# dw08a4lyr.net
KiCad netlist of a schematic drawn in EAGLE
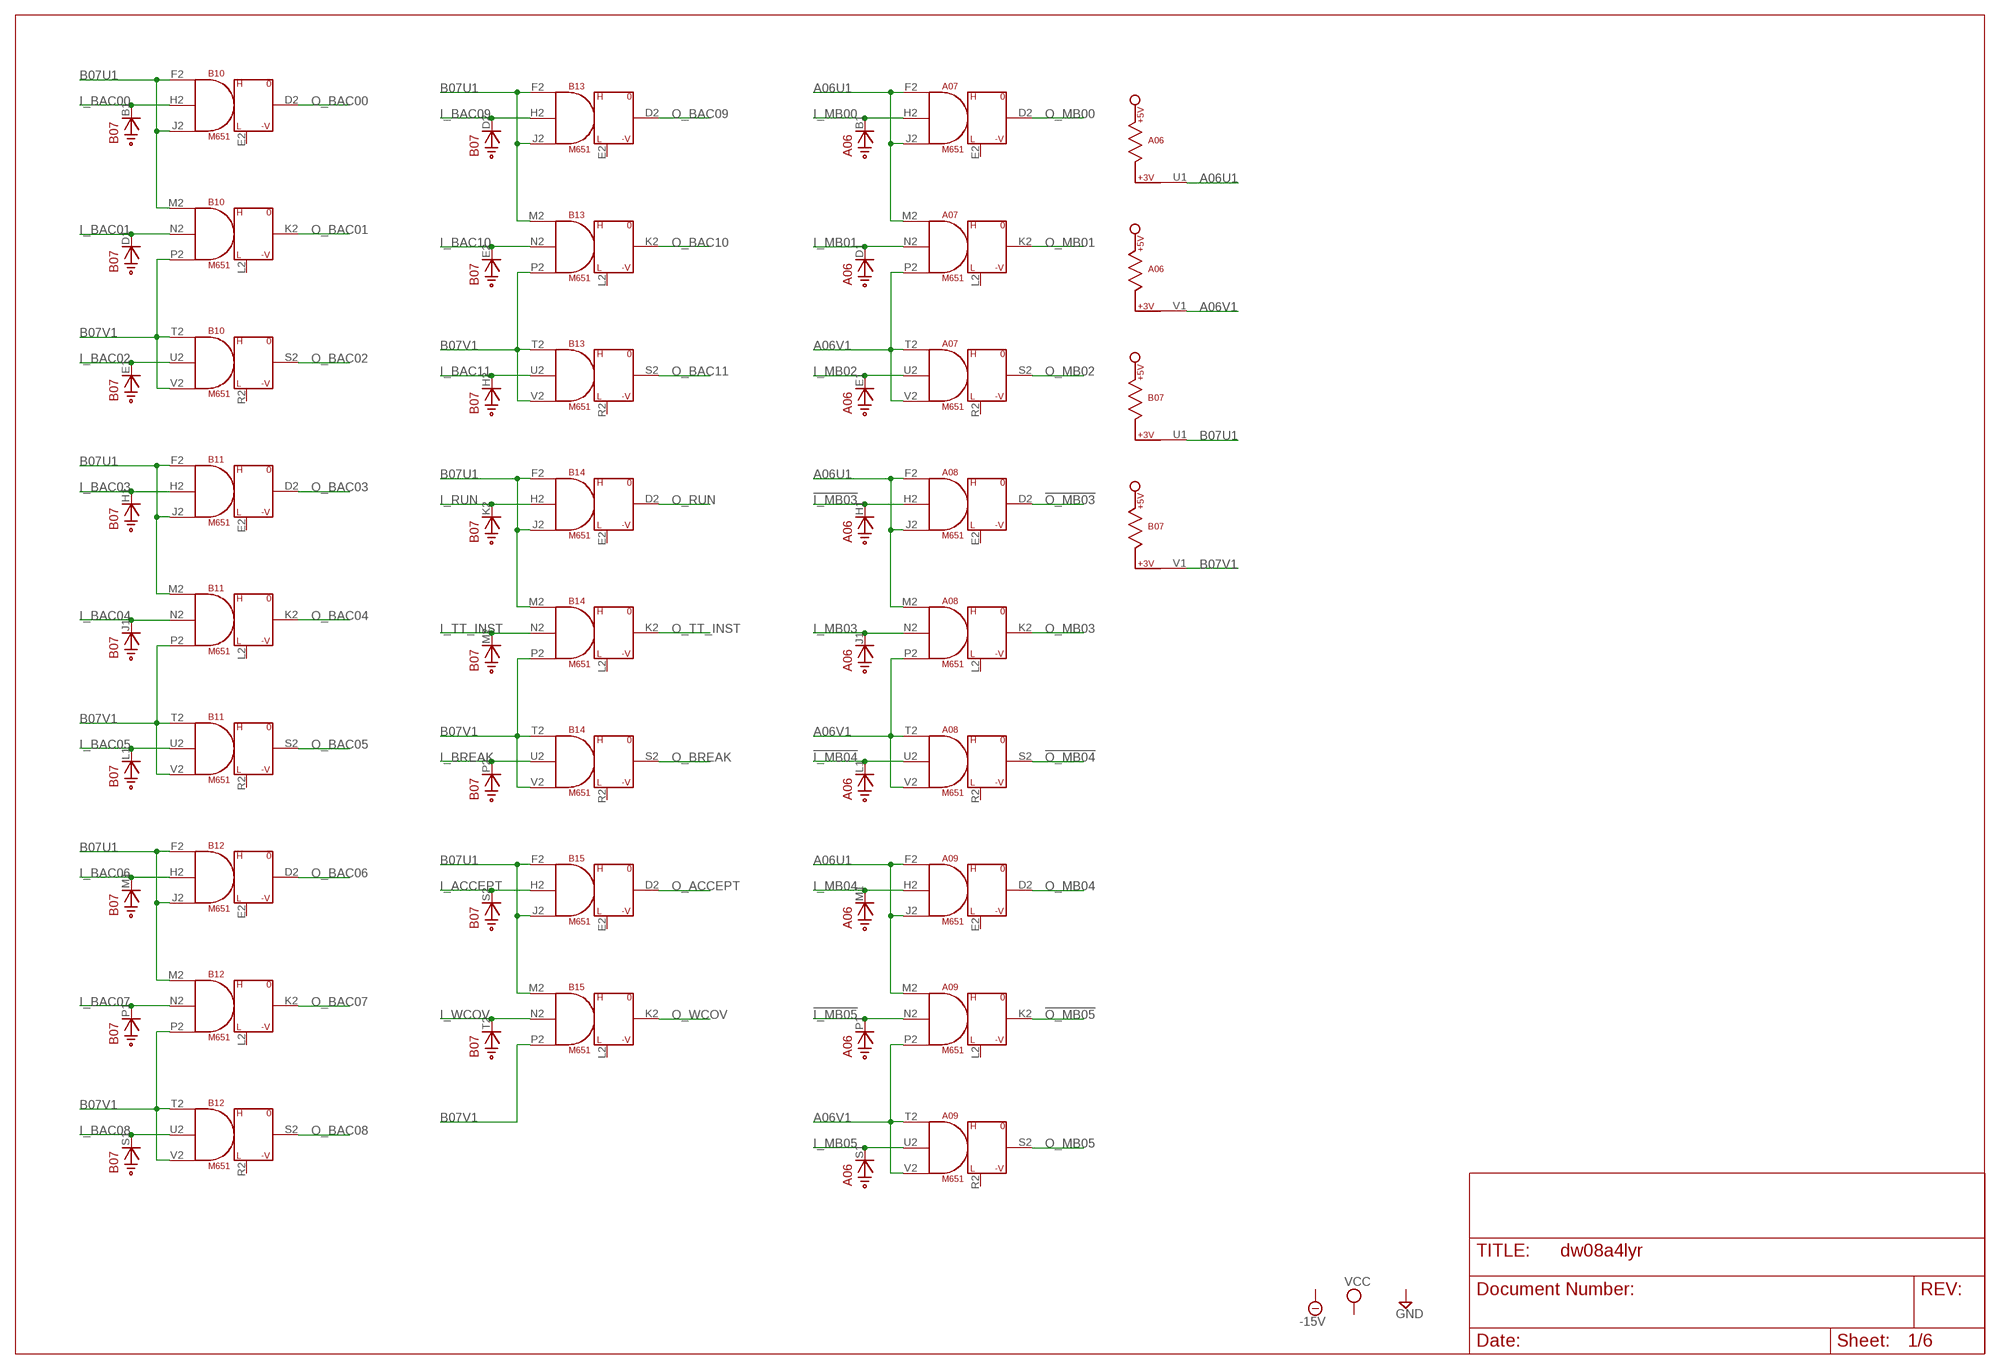
[diagram p0: schematic, sheet 1]
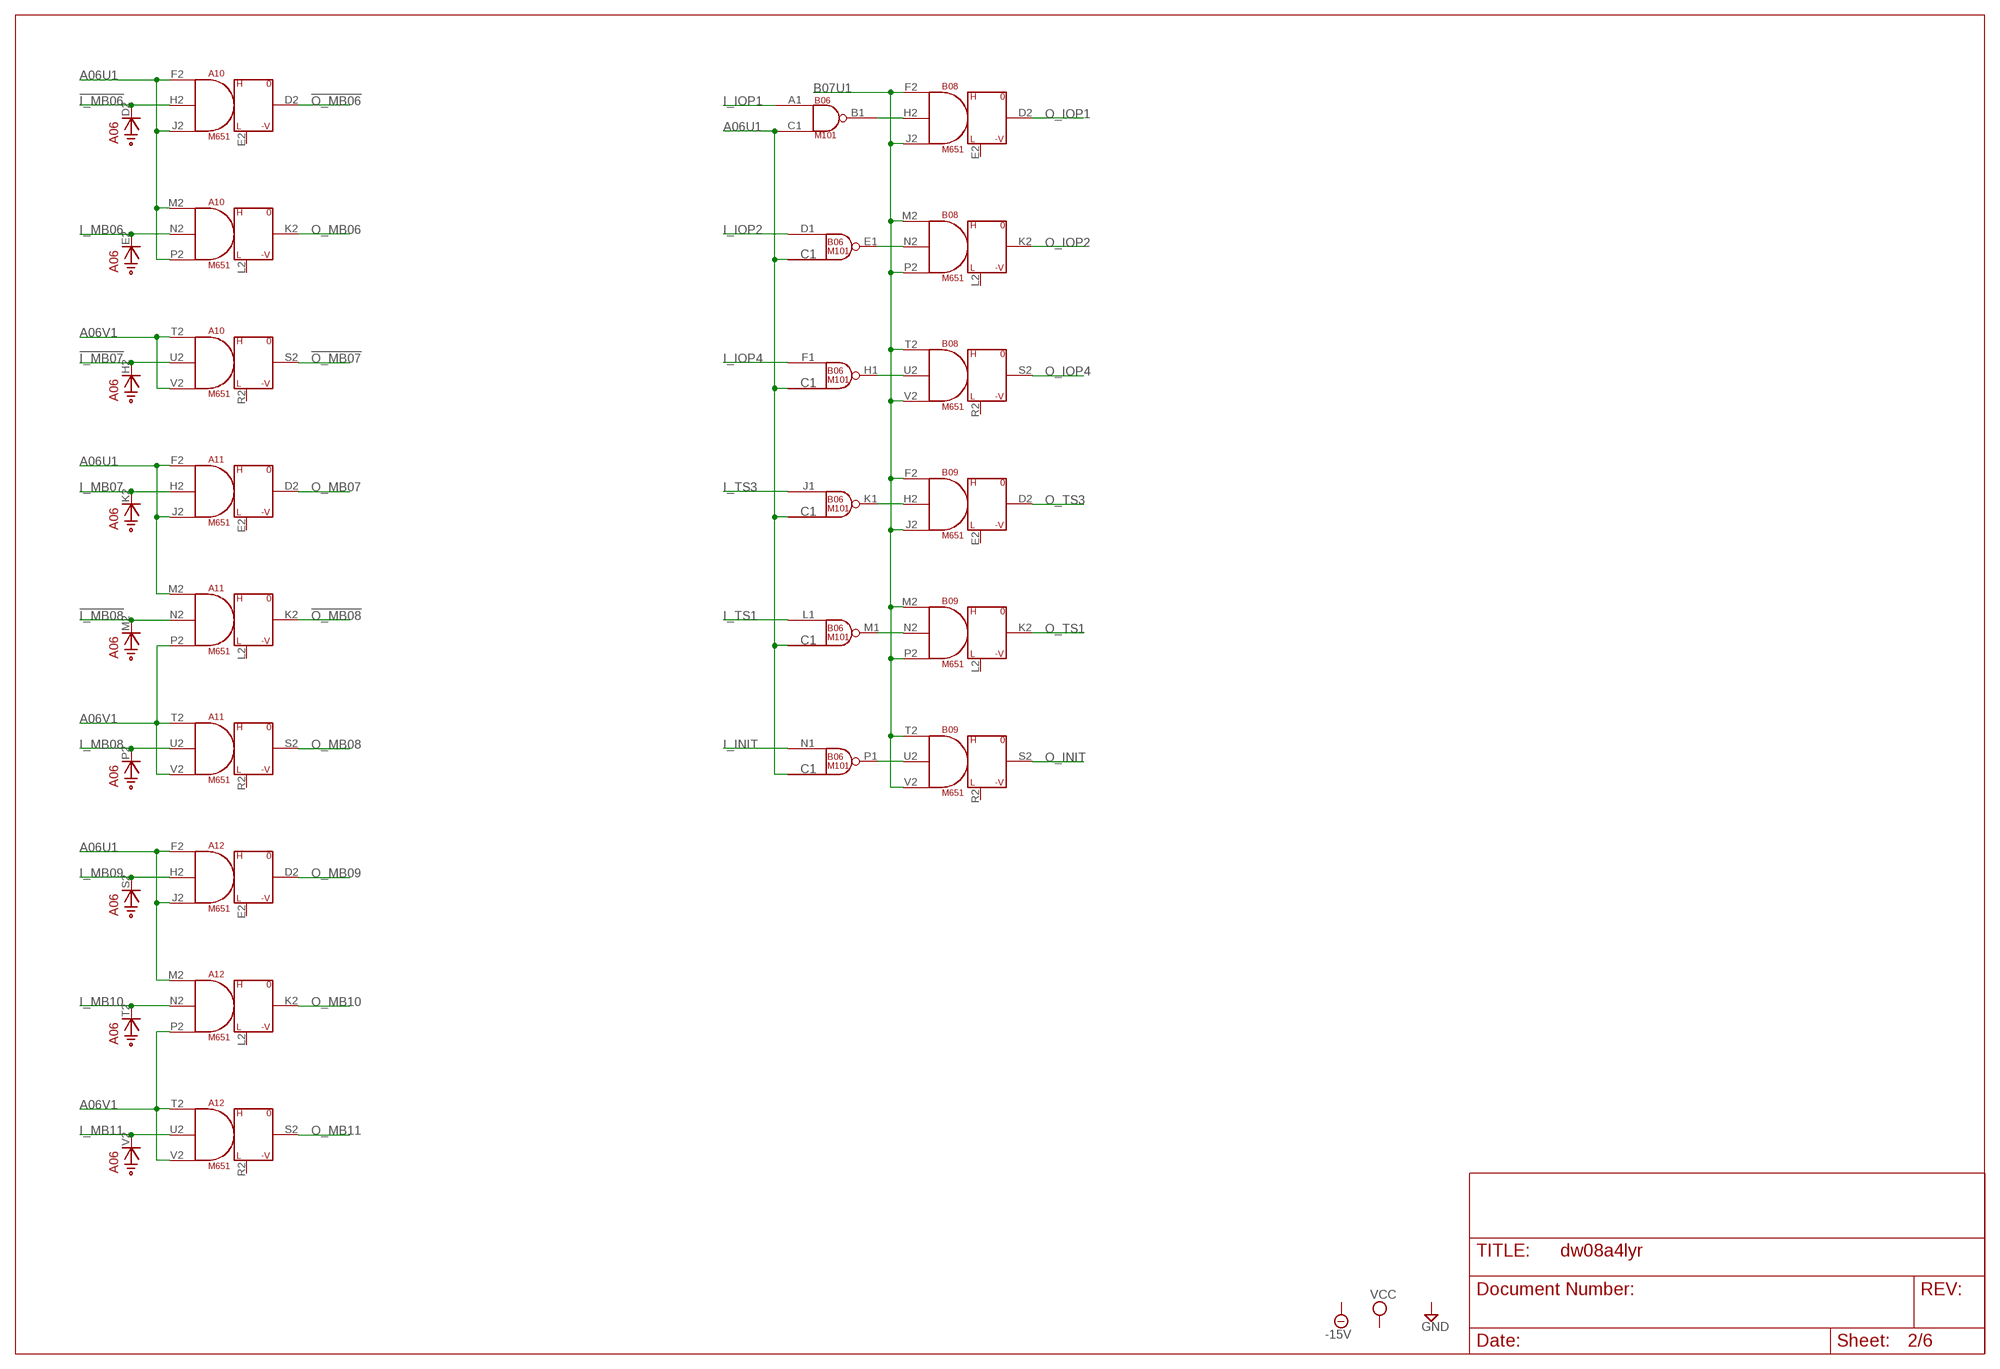
[diagram p1: schematic, sheet 2]
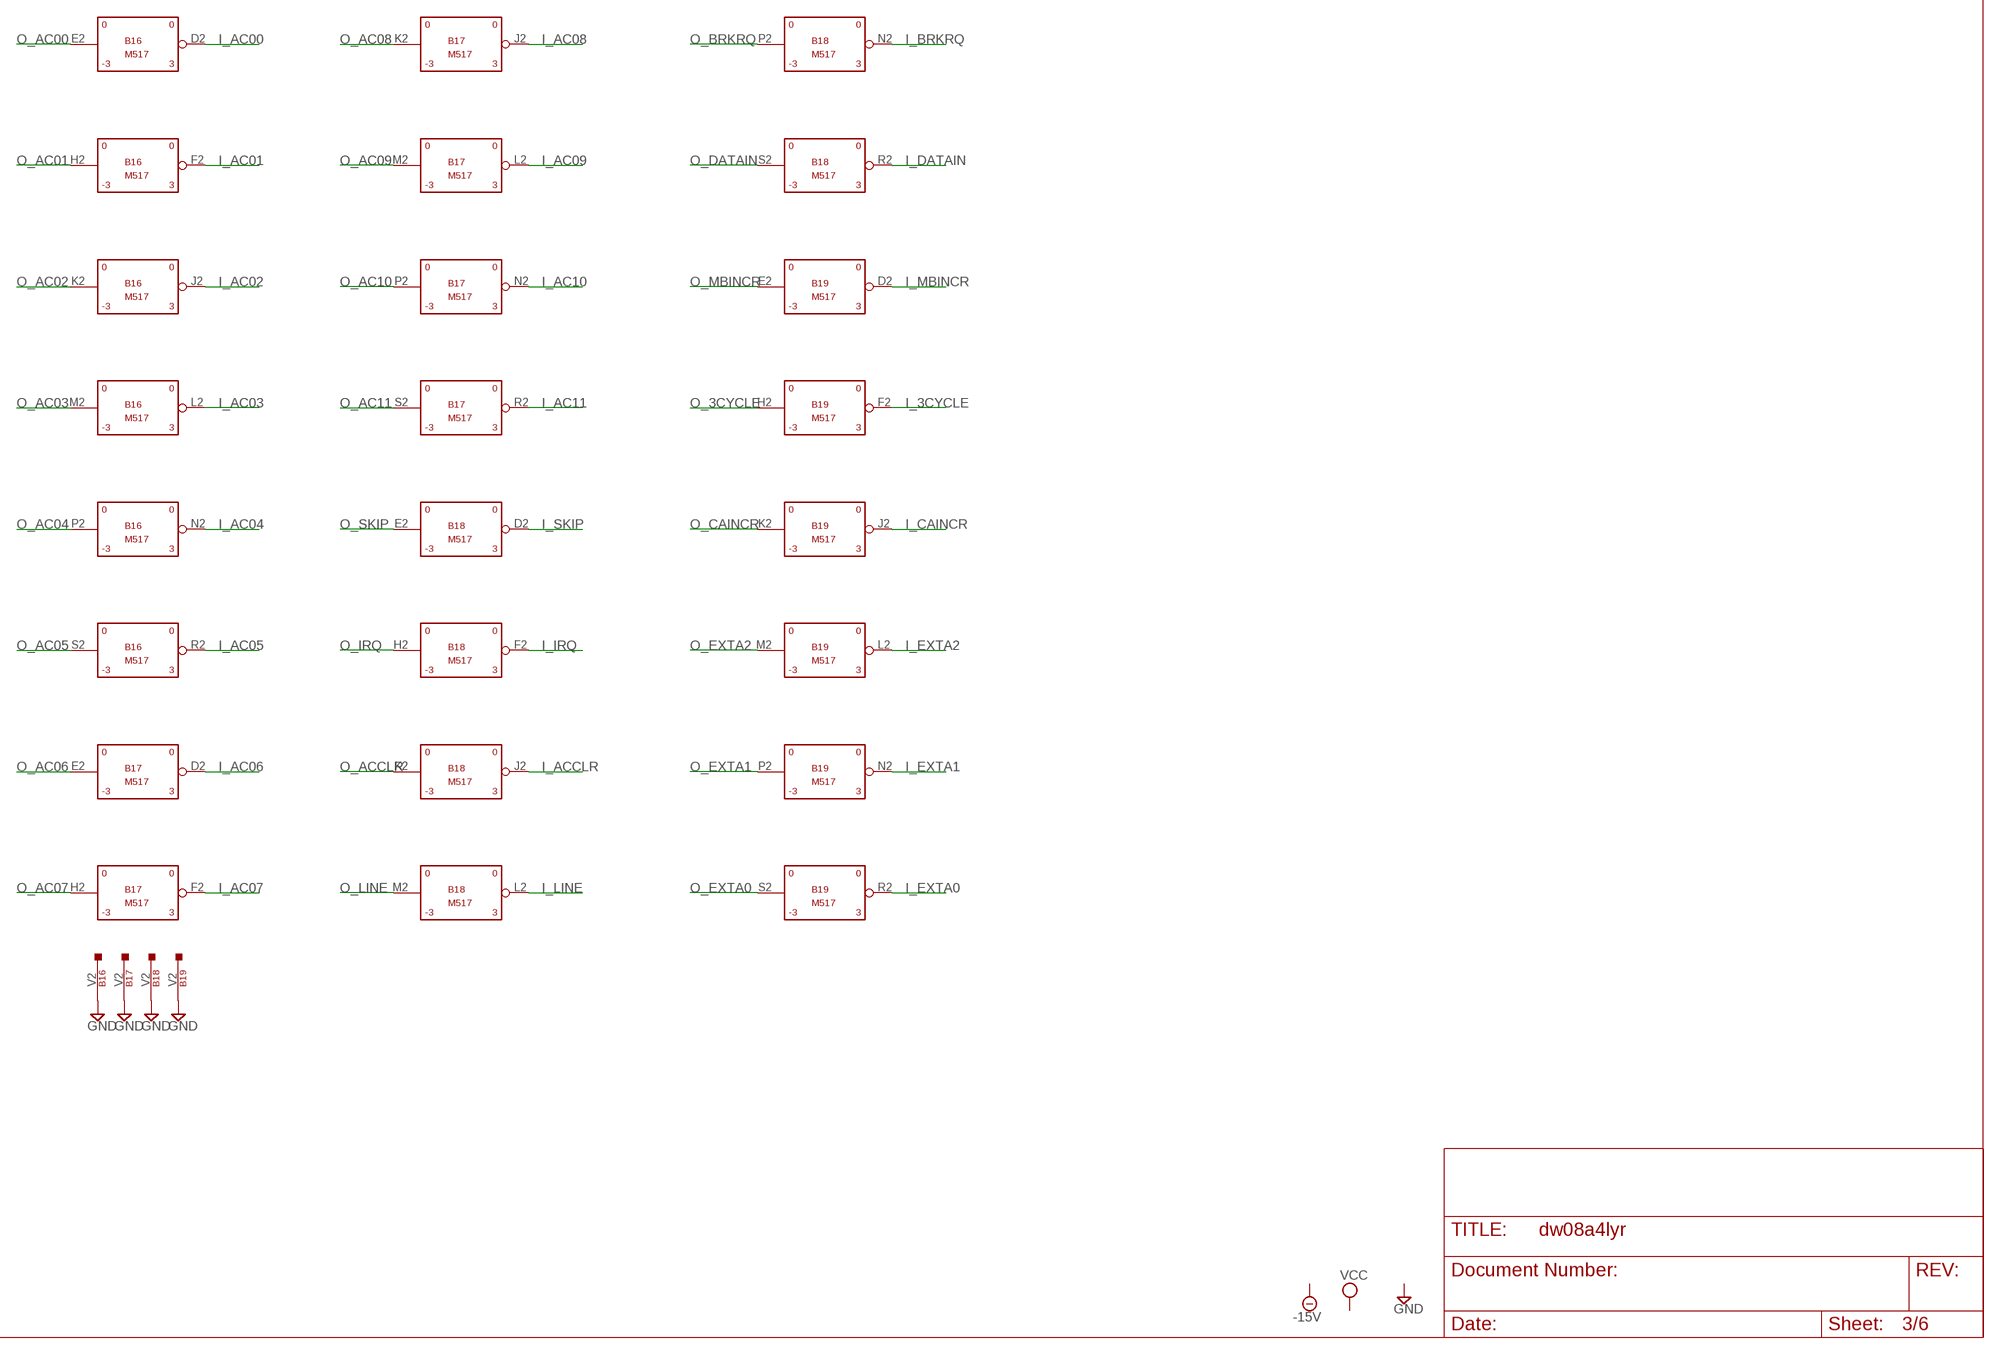
[diagram p2: schematic, sheet 3]
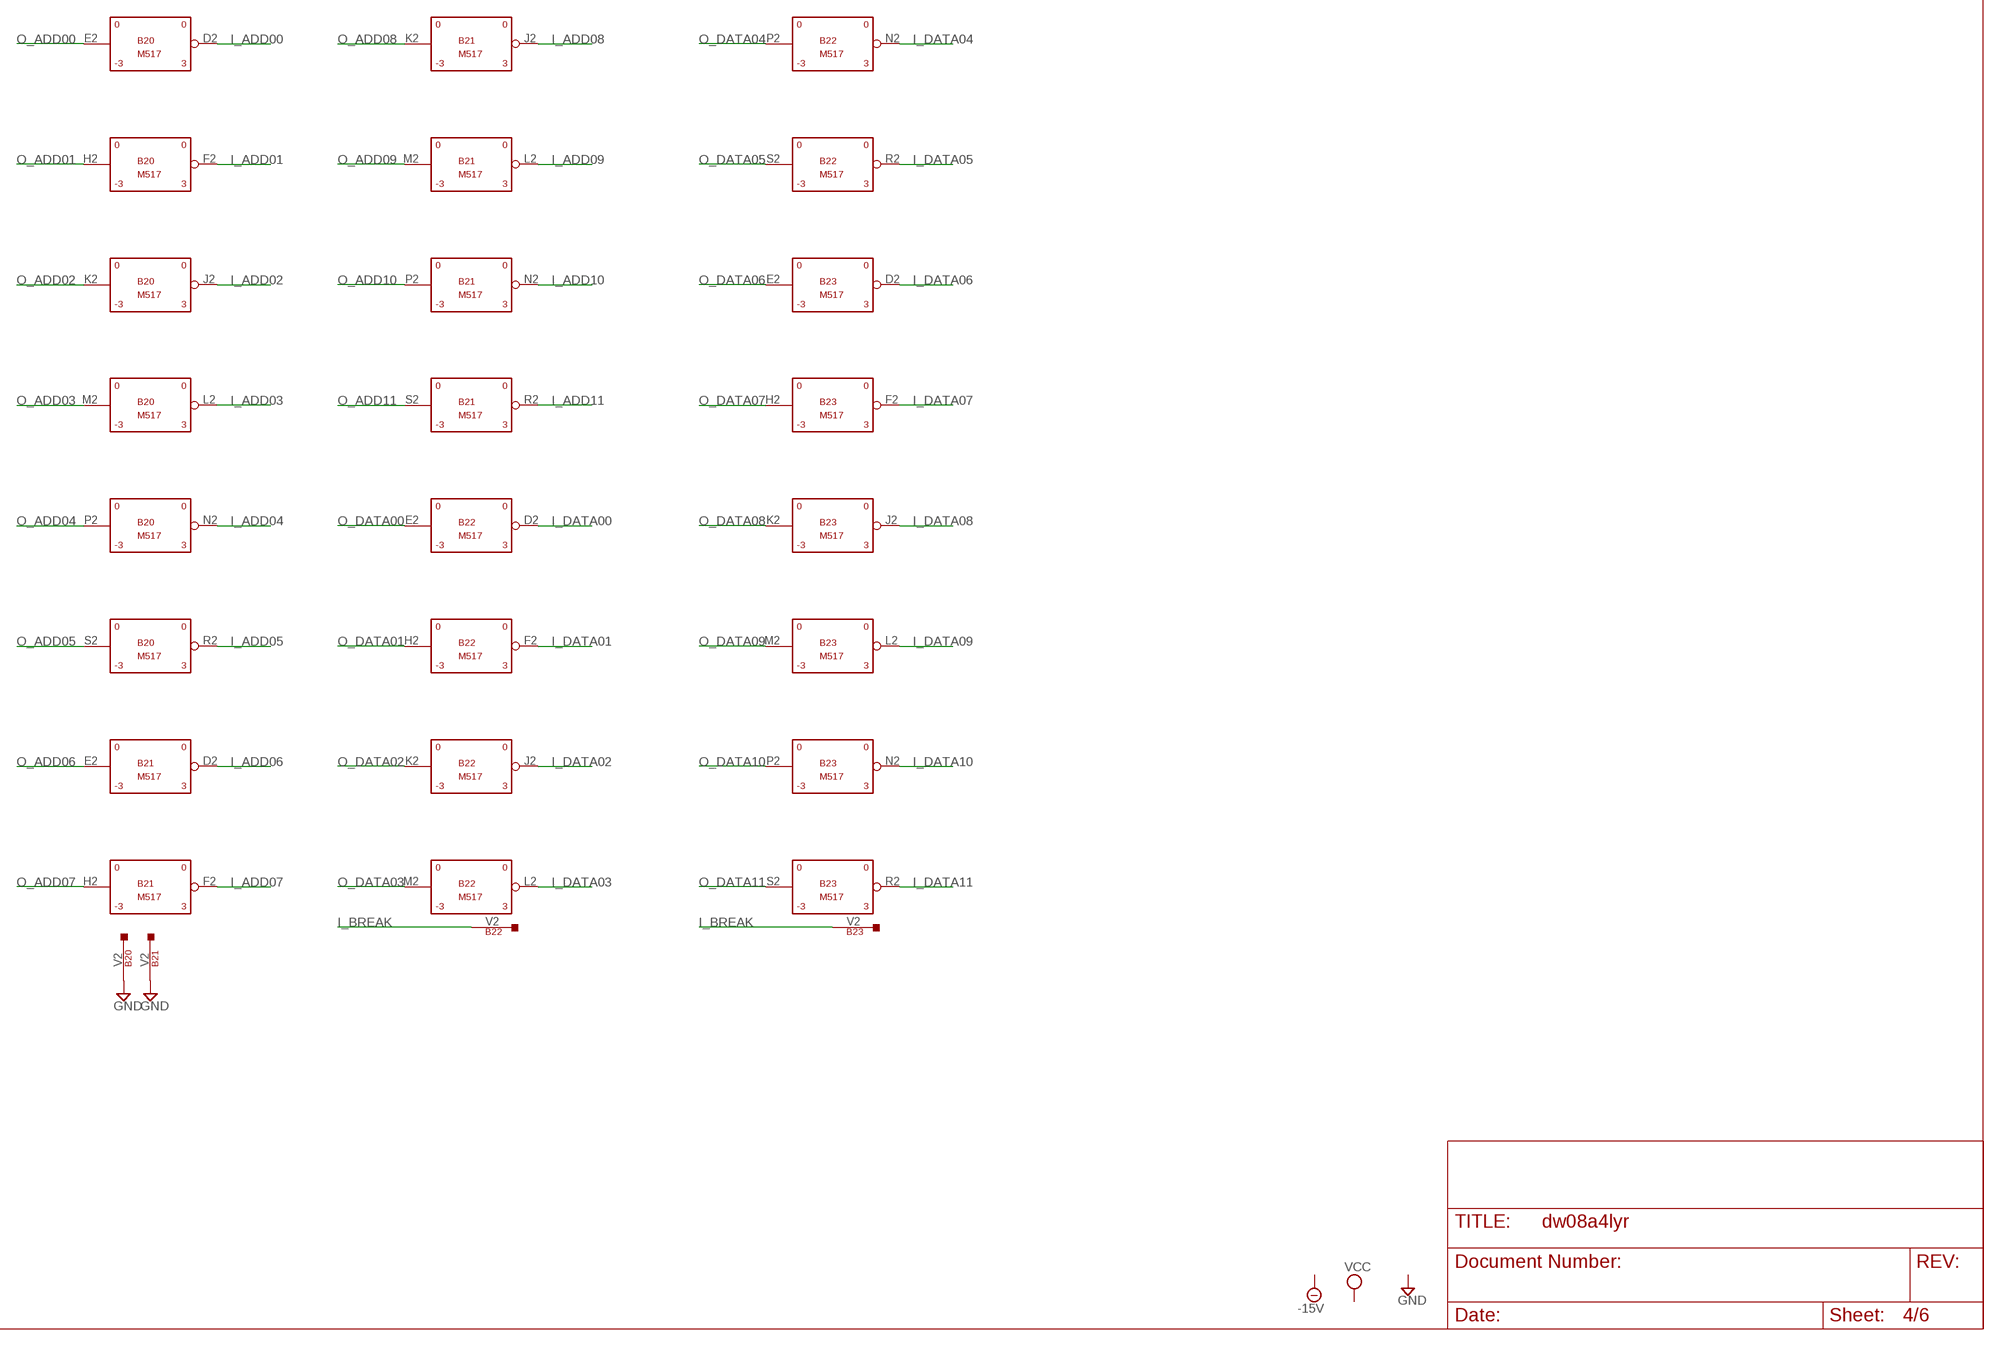
[diagram p3: schematic, sheet 4]
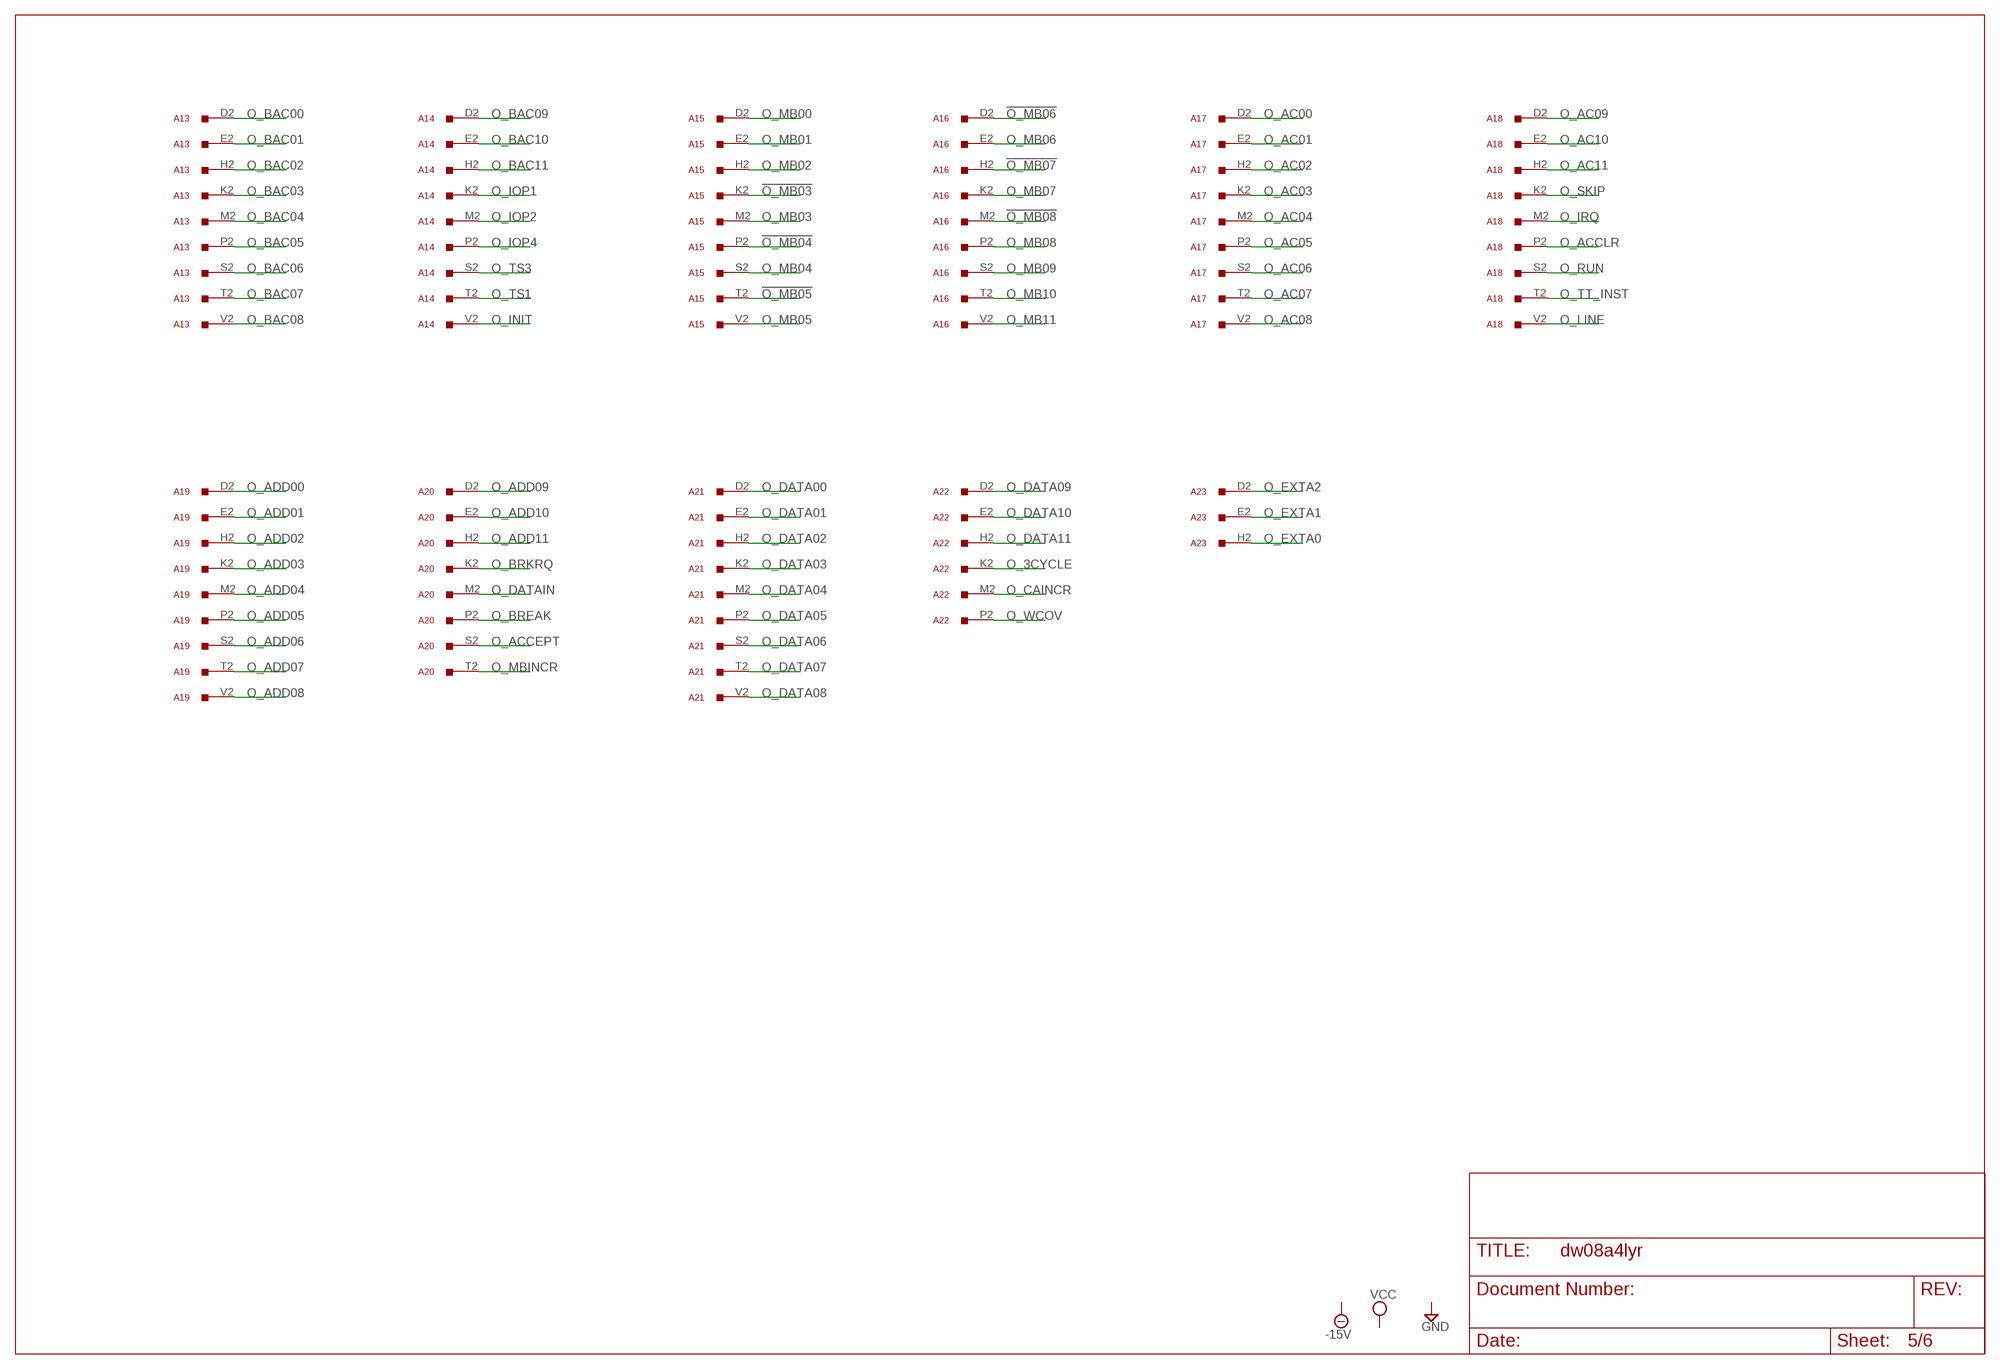
[diagram p4: schematic, sheet 5]
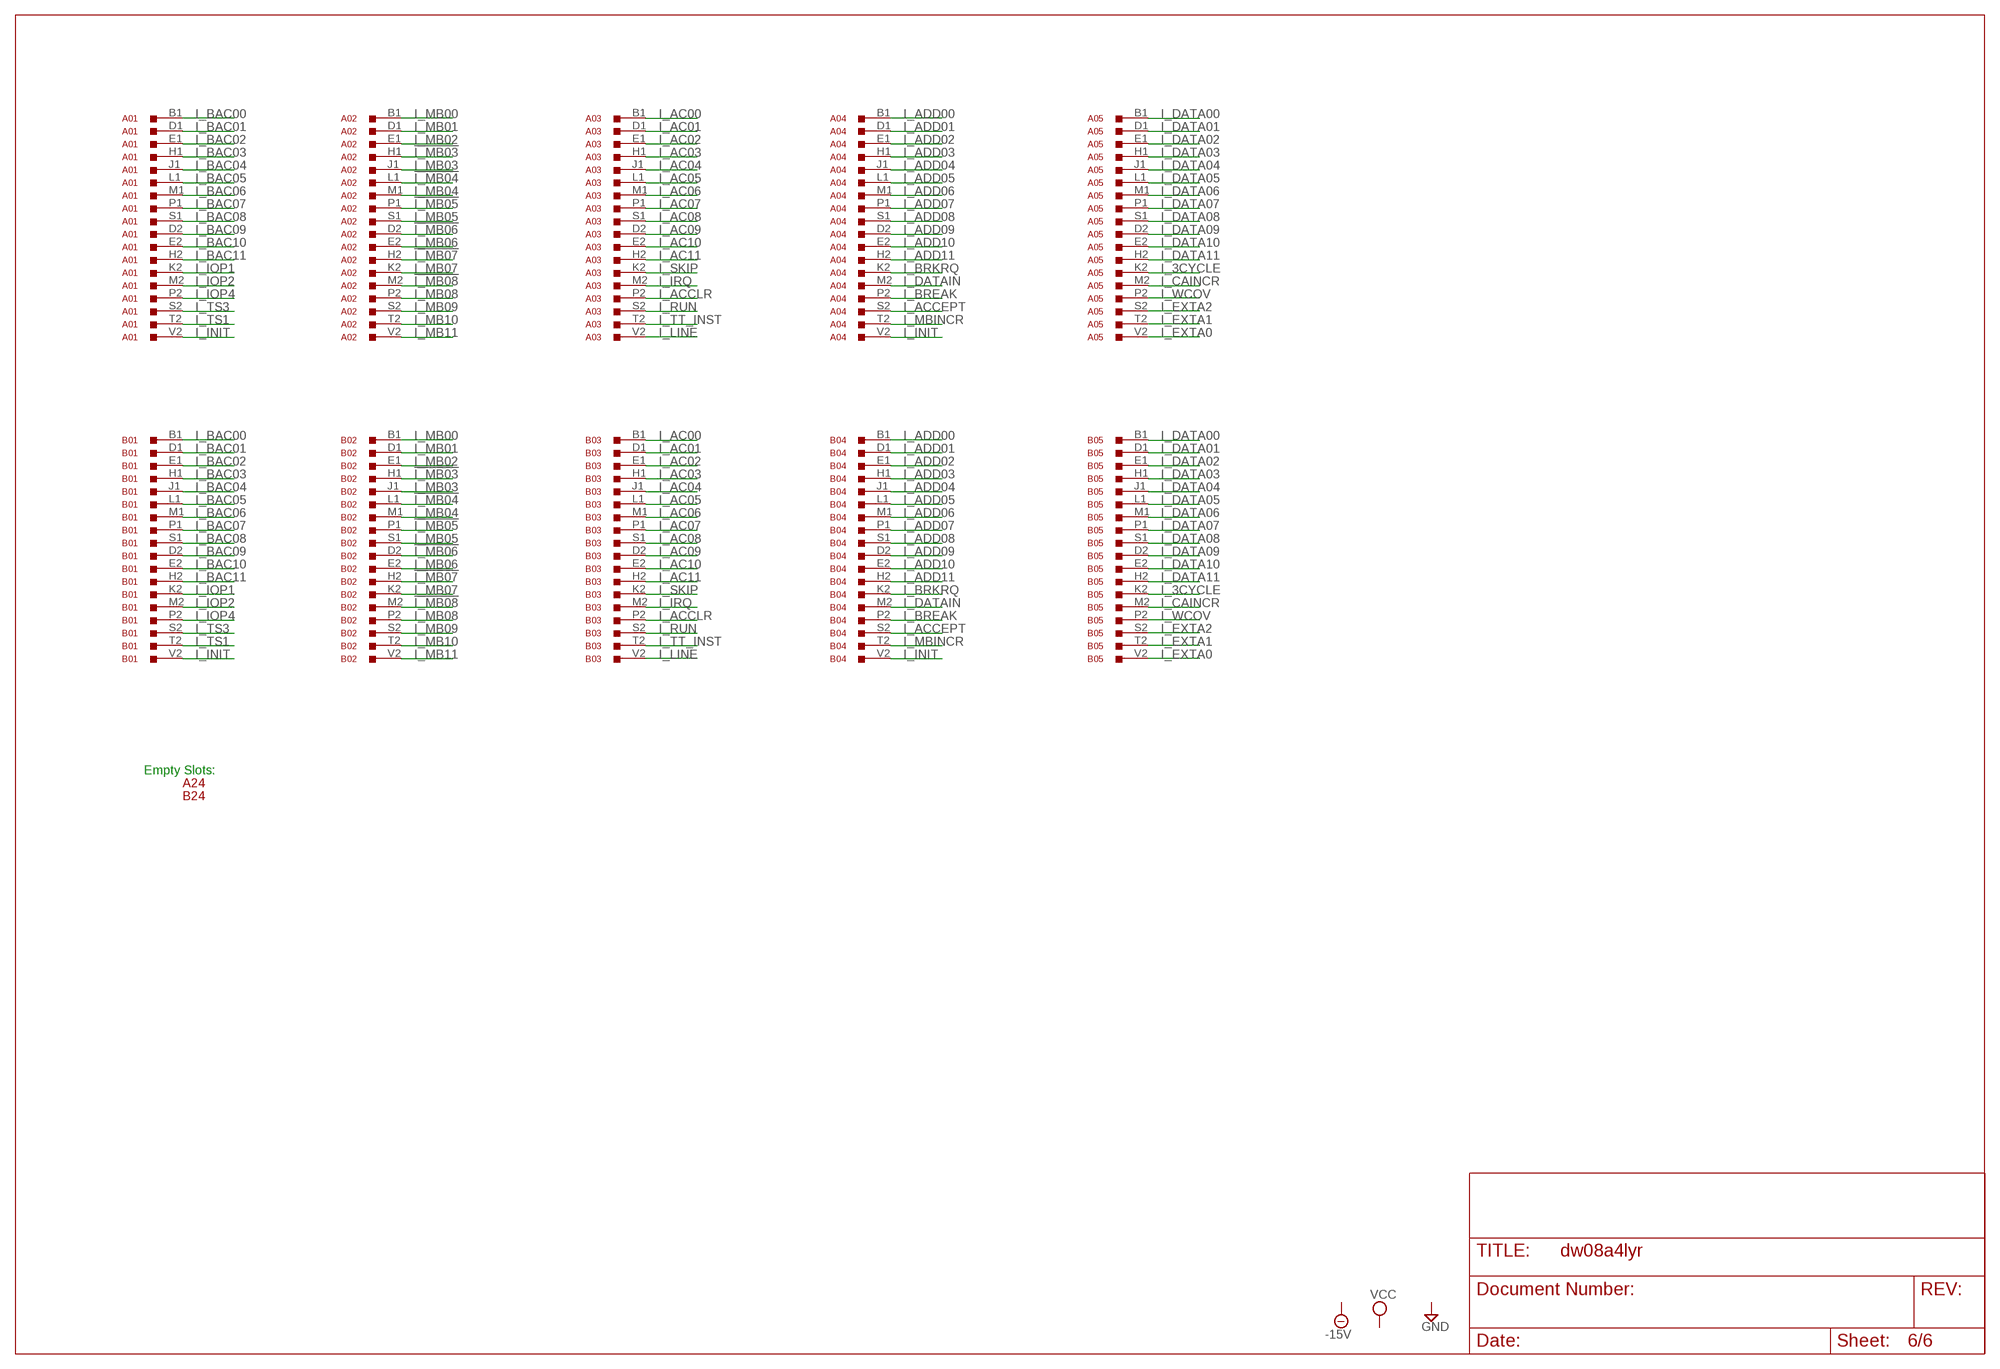
[diagram p5: schematic, sheet 6]

(export (version "E")
  (design (tool "Eeschema 10.0.6"))
  (components
    (comp (ref "A06")
      (value "M907")
      (footprint "eagle-import:H807")
      (libsource (lib "eagle-import") (part "M907"))
    )
    (comp (ref "A10")
      (value "M651")
      (footprint "eagle-import:H807")
      (libsource (lib "eagle-import") (part "M651"))
    )
    (comp (ref "A11")
      (value "M651")
      (footprint "eagle-import:H807")
      (libsource (lib "eagle-import") (part "M651"))
    )
    (comp (ref "A12")
      (value "M651")
      (footprint "eagle-import:H807")
      (libsource (lib "eagle-import") (part "M651"))
    )
    (comp (ref "B06")
      (value "M101")
      (footprint "eagle-import:H807")
      (libsource (lib "eagle-import") (part "M101"))
    )
    (comp (ref "B08")
      (value "M651")
      (footprint "eagle-import:H807")
      (libsource (lib "eagle-import") (part "M651"))
    )
    (comp (ref "B09")
      (value "M651")
      (footprint "eagle-import:H807")
      (libsource (lib "eagle-import") (part "M651"))
    )
    (comp (ref "A01")
      (value "M903")
      (footprint "eagle-import:H807")
      (libsource (lib "eagle-import") (part "M903"))
    )
    (comp (ref "A02")
      (value "M903")
      (footprint "eagle-import:H807")
      (libsource (lib "eagle-import") (part "M903"))
    )
    (comp (ref "A03")
      (value "M903")
      (footprint "eagle-import:H807")
      (libsource (lib "eagle-import") (part "M903"))
    )
    (comp (ref "A04")
      (value "M903")
      (footprint "eagle-import:H807")
      (libsource (lib "eagle-import") (part "M903"))
    )
    (comp (ref "A05")
      (value "M903")
      (footprint "eagle-import:H807")
      (libsource (lib "eagle-import") (part "M903"))
    )
    (comp (ref "A24")
      (value "H807")
      (footprint "eagle-import:H807")
      (libsource (lib "eagle-import") (part "H807"))
    )
    (comp (ref "B01")
      (value "M903")
      (footprint "eagle-import:H807")
      (libsource (lib "eagle-import") (part "M903"))
    )
    (comp (ref "B02")
      (value "M903")
      (footprint "eagle-import:H807")
      (libsource (lib "eagle-import") (part "M903"))
    )
    (comp (ref "B03")
      (value "M903")
      (footprint "eagle-import:H807")
      (libsource (lib "eagle-import") (part "M903"))
    )
    (comp (ref "B04")
      (value "M903")
      (footprint "eagle-import:H807")
      (libsource (lib "eagle-import") (part "M903"))
    )
    (comp (ref "B05")
      (value "M903")
      (footprint "eagle-import:H807")
      (libsource (lib "eagle-import") (part "M903"))
    )
    (comp (ref "B24")
      (value "H807")
      (footprint "eagle-import:H807")
      (libsource (lib "eagle-import") (part "H807"))
    )
    (comp (ref "A07")
      (value "M651")
      (footprint "eagle-import:H807")
      (libsource (lib "eagle-import") (part "M651"))
    )
    (comp (ref "A08")
      (value "M651")
      (footprint "eagle-import:H807")
      (libsource (lib "eagle-import") (part "M651"))
    )
    (comp (ref "A09")
      (value "M651")
      (footprint "eagle-import:H807")
      (libsource (lib "eagle-import") (part "M651"))
    )
    (comp (ref "B07")
      (value "M907")
      (footprint "eagle-import:H807")
      (libsource (lib "eagle-import") (part "M907"))
    )
    (comp (ref "B10")
      (value "M651")
      (footprint "eagle-import:H807")
      (libsource (lib "eagle-import") (part "M651"))
    )
    (comp (ref "B11")
      (value "M651")
      (footprint "eagle-import:H807")
      (libsource (lib "eagle-import") (part "M651"))
    )
    (comp (ref "B12")
      (value "M651")
      (footprint "eagle-import:H807")
      (libsource (lib "eagle-import") (part "M651"))
    )
    (comp (ref "B13")
      (value "M651")
      (footprint "eagle-import:H807")
      (libsource (lib "eagle-import") (part "M651"))
    )
    (comp (ref "B14")
      (value "M651")
      (footprint "eagle-import:H807")
      (libsource (lib "eagle-import") (part "M651"))
    )
    (comp (ref "B15")
      (value "M651")
      (footprint "eagle-import:H807")
      (libsource (lib "eagle-import") (part "M651"))
    )
    (comp (ref "B20")
      (value "M517")
      (footprint "eagle-import:H807")
      (libsource (lib "eagle-import") (part "M517"))
    )
    (comp (ref "B21")
      (value "M517")
      (footprint "eagle-import:H807")
      (libsource (lib "eagle-import") (part "M517"))
    )
    (comp (ref "B22")
      (value "M517")
      (footprint "eagle-import:H807")
      (libsource (lib "eagle-import") (part "M517"))
    )
    (comp (ref "B23")
      (value "M517")
      (footprint "eagle-import:H807")
      (libsource (lib "eagle-import") (part "M517"))
    )
    (comp (ref "A13")
      (value "W011")
      (footprint "eagle-import:H807")
      (libsource (lib "eagle-import") (part "W011"))
    )
    (comp (ref "A14")
      (value "W011")
      (footprint "eagle-import:H807")
      (libsource (lib "eagle-import") (part "W011"))
    )
    (comp (ref "A15")
      (value "W011")
      (footprint "eagle-import:H807")
      (libsource (lib "eagle-import") (part "W011"))
    )
    (comp (ref "A16")
      (value "W011")
      (footprint "eagle-import:H807")
      (libsource (lib "eagle-import") (part "W011"))
    )
    (comp (ref "A17")
      (value "W011")
      (footprint "eagle-import:H807")
      (libsource (lib "eagle-import") (part "W011"))
    )
    (comp (ref "A18")
      (value "W011")
      (footprint "eagle-import:H807")
      (libsource (lib "eagle-import") (part "W011"))
    )
    (comp (ref "A19")
      (value "W011")
      (footprint "eagle-import:H807")
      (libsource (lib "eagle-import") (part "W011"))
    )
    (comp (ref "A20")
      (value "W011")
      (footprint "eagle-import:H807")
      (libsource (lib "eagle-import") (part "W011"))
    )
    (comp (ref "A21")
      (value "W011")
      (footprint "eagle-import:H807")
      (libsource (lib "eagle-import") (part "W011"))
    )
    (comp (ref "A22")
      (value "W011")
      (footprint "eagle-import:H807")
      (libsource (lib "eagle-import") (part "W011"))
    )
    (comp (ref "A23")
      (value "W011")
      (footprint "eagle-import:H807")
      (libsource (lib "eagle-import") (part "W011"))
    )
    (comp (ref "B16")
      (value "M517")
      (footprint "eagle-import:H807")
      (libsource (lib "eagle-import") (part "M517"))
    )
    (comp (ref "B17")
      (value "M517")
      (footprint "eagle-import:H807")
      (libsource (lib "eagle-import") (part "M517"))
    )
    (comp (ref "B18")
      (value "M517")
      (footprint "eagle-import:H807")
      (libsource (lib "eagle-import") (part "M517"))
    )
    (comp (ref "B19")
      (value "M517")
      (footprint "eagle-import:H807")
      (libsource (lib "eagle-import") (part "M517"))
    )
  )
  (nets
    (net (code "2") (name "A06U1") (class "Default")
      (node (ref "A06") (pin "U1") (pinfunction "P$1_U1") (pintype "passive"))
      (node (ref "A07") (pin "F2") (pinfunction "IN1_F2") (pintype "input"))
      (node (ref "A07") (pin "J2") (pinfunction "IN3_J2") (pintype "input"))
      (node (ref "A07") (pin "M2") (pinfunction "IN1_M2") (pintype "input"))
      (node (ref "A08") (pin "F2") (pinfunction "IN1_F2") (pintype "input"))
      (node (ref "A08") (pin "J2") (pinfunction "IN3_J2") (pintype "input"))
      (node (ref "A08") (pin "M2") (pinfunction "IN1_M2") (pintype "input"))
      (node (ref "A09") (pin "F2") (pinfunction "IN1_F2") (pintype "input"))
      (node (ref "A09") (pin "J2") (pinfunction "IN3_J2") (pintype "input"))
      (node (ref "A09") (pin "M2") (pinfunction "IN1_M2") (pintype "input"))
      (node (ref "A10") (pin "F2") (pinfunction "IN1_F2") (pintype "input"))
      (node (ref "A10") (pin "J2") (pinfunction "IN3_J2") (pintype "input"))
      (node (ref "A10") (pin "M2") (pinfunction "IN1_M2") (pintype "input"))
      (node (ref "A10") (pin "P2") (pinfunction "IN3_P2") (pintype "input"))
      (node (ref "A11") (pin "F2") (pinfunction "IN1_F2") (pintype "input"))
      (node (ref "A11") (pin "J2") (pinfunction "IN3_J2") (pintype "input"))
      (node (ref "A11") (pin "M2") (pinfunction "IN1_M2") (pintype "input"))
      (node (ref "A12") (pin "F2") (pinfunction "IN1_F2") (pintype "input"))
      (node (ref "A12") (pin "J2") (pinfunction "IN3_J2") (pintype "input"))
      (node (ref "A12") (pin "M2") (pinfunction "IN1_M2") (pintype "input"))
      (node (ref "B06") (pin "C1") (pinfunction "IN2_C1") (pintype "input"))
    )
    (net (code "3") (name "A06V1") (class "Default")
      (node (ref "A06") (pin "V1") (pinfunction "P$1_V1") (pintype "passive"))
      (node (ref "A07") (pin "P2") (pinfunction "IN3_P2") (pintype "input"))
      (node (ref "A07") (pin "T2") (pinfunction "IN1_T2") (pintype "input"))
      (node (ref "A07") (pin "V2") (pinfunction "IN3_V2") (pintype "input"))
      (node (ref "A08") (pin "P2") (pinfunction "IN3_P2") (pintype "input"))
      (node (ref "A08") (pin "T2") (pinfunction "IN1_T2") (pintype "input"))
      (node (ref "A08") (pin "V2") (pinfunction "IN3_V2") (pintype "input"))
      (node (ref "A09") (pin "P2") (pinfunction "IN3_P2") (pintype "input"))
      (node (ref "A09") (pin "T2") (pinfunction "IN1_T2") (pintype "input"))
      (node (ref "A09") (pin "V2") (pinfunction "IN3_V2") (pintype "input"))
      (node (ref "A10") (pin "T2") (pinfunction "IN1_T2") (pintype "input"))
      (node (ref "A10") (pin "V2") (pinfunction "IN3_V2") (pintype "input"))
      (node (ref "A11") (pin "P2") (pinfunction "IN3_P2") (pintype "input"))
      (node (ref "A11") (pin "T2") (pinfunction "IN1_T2") (pintype "input"))
      (node (ref "A11") (pin "V2") (pinfunction "IN3_V2") (pintype "input"))
      (node (ref "A12") (pin "P2") (pinfunction "IN3_P2") (pintype "input"))
      (node (ref "A12") (pin "T2") (pinfunction "IN1_T2") (pintype "input"))
      (node (ref "A12") (pin "V2") (pinfunction "IN3_V2") (pintype "input"))
    )
    (net (code "4") (name "B07U1") (class "Default")
      (node (ref "B07") (pin "U1") (pinfunction "P$1_U1") (pintype "passive"))
      (node (ref "B08") (pin "F2") (pinfunction "IN1_F2") (pintype "input"))
      (node (ref "B08") (pin "J2") (pinfunction "IN3_J2") (pintype "input"))
      (node (ref "B08") (pin "M2") (pinfunction "IN1_M2") (pintype "input"))
      (node (ref "B08") (pin "P2") (pinfunction "IN3_P2") (pintype "input"))
      (node (ref "B08") (pin "T2") (pinfunction "IN1_T2") (pintype "input"))
      (node (ref "B08") (pin "V2") (pinfunction "IN3_V2") (pintype "input"))
      (node (ref "B09") (pin "F2") (pinfunction "IN1_F2") (pintype "input"))
      (node (ref "B09") (pin "J2") (pinfunction "IN3_J2") (pintype "input"))
      (node (ref "B09") (pin "M2") (pinfunction "IN1_M2") (pintype "input"))
      (node (ref "B09") (pin "P2") (pinfunction "IN3_P2") (pintype "input"))
      (node (ref "B09") (pin "T2") (pinfunction "IN1_T2") (pintype "input"))
      (node (ref "B09") (pin "V2") (pinfunction "IN3_V2") (pintype "input"))
      (node (ref "B10") (pin "F2") (pinfunction "IN1_F2") (pintype "input"))
      (node (ref "B10") (pin "J2") (pinfunction "IN3_J2") (pintype "input"))
      (node (ref "B10") (pin "M2") (pinfunction "IN1_M2") (pintype "input"))
      (node (ref "B11") (pin "F2") (pinfunction "IN1_F2") (pintype "input"))
      (node (ref "B11") (pin "J2") (pinfunction "IN3_J2") (pintype "input"))
      (node (ref "B11") (pin "M2") (pinfunction "IN1_M2") (pintype "input"))
      (node (ref "B12") (pin "F2") (pinfunction "IN1_F2") (pintype "input"))
      (node (ref "B12") (pin "J2") (pinfunction "IN3_J2") (pintype "input"))
      (node (ref "B12") (pin "M2") (pinfunction "IN1_M2") (pintype "input"))
      (node (ref "B13") (pin "F2") (pinfunction "IN1_F2") (pintype "input"))
      (node (ref "B13") (pin "J2") (pinfunction "IN3_J2") (pintype "input"))
      (node (ref "B13") (pin "M2") (pinfunction "IN1_M2") (pintype "input"))
      (node (ref "B14") (pin "F2") (pinfunction "IN1_F2") (pintype "input"))
      (node (ref "B14") (pin "J2") (pinfunction "IN3_J2") (pintype "input"))
      (node (ref "B14") (pin "M2") (pinfunction "IN1_M2") (pintype "input"))
      (node (ref "B15") (pin "F2") (pinfunction "IN1_F2") (pintype "input"))
      (node (ref "B15") (pin "J2") (pinfunction "IN3_J2") (pintype "input"))
      (node (ref "B15") (pin "M2") (pinfunction "IN1_M2") (pintype "input"))
    )
    (net (code "5") (name "B07V1") (class "Default")
      (node (ref "B07") (pin "V1") (pinfunction "P$1_V1") (pintype "passive"))
      (node (ref "B10") (pin "P2") (pinfunction "IN3_P2") (pintype "input"))
      (node (ref "B10") (pin "T2") (pinfunction "IN1_T2") (pintype "input"))
      (node (ref "B10") (pin "V2") (pinfunction "IN3_V2") (pintype "input"))
      (node (ref "B11") (pin "P2") (pinfunction "IN3_P2") (pintype "input"))
      (node (ref "B11") (pin "T2") (pinfunction "IN1_T2") (pintype "input"))
      (node (ref "B11") (pin "V2") (pinfunction "IN3_V2") (pintype "input"))
      (node (ref "B12") (pin "P2") (pinfunction "IN3_P2") (pintype "input"))
      (node (ref "B12") (pin "T2") (pinfunction "IN1_T2") (pintype "input"))
      (node (ref "B12") (pin "V2") (pinfunction "IN3_V2") (pintype "input"))
      (node (ref "B13") (pin "P2") (pinfunction "IN3_P2") (pintype "input"))
      (node (ref "B13") (pin "T2") (pinfunction "IN1_T2") (pintype "input"))
      (node (ref "B13") (pin "V2") (pinfunction "IN3_V2") (pintype "input"))
      (node (ref "B14") (pin "P2") (pinfunction "IN3_P2") (pintype "input"))
      (node (ref "B14") (pin "T2") (pinfunction "IN1_T2") (pintype "input"))
      (node (ref "B14") (pin "V2") (pinfunction "IN3_V2") (pintype "input"))
      (node (ref "B15") (pin "P2") (pinfunction "IN3_P2") (pintype "input"))
    )
    (net (code "6") (name "GND") (class "Default")
      (node (ref "B16") (pin "V2") (pinfunction "P$1_V2") (pintype "input"))
      (node (ref "B17") (pin "V2") (pinfunction "P$1_V2") (pintype "input"))
      (node (ref "B18") (pin "V2") (pinfunction "P$1_V2") (pintype "input"))
      (node (ref "B19") (pin "V2") (pinfunction "P$1_V2") (pintype "input"))
      (node (ref "B20") (pin "V2") (pinfunction "P$1_V2") (pintype "input"))
      (node (ref "B21") (pin "V2") (pinfunction "P$1_V2") (pintype "input"))
    )
    (net (code "7") (name "I_3CYCLE") (class "Default")
      (node (ref "A05") (pin "K2") (pinfunction "P$2_K2") (pintype "bidirectional"))
      (node (ref "B05") (pin "K2") (pinfunction "P$2_K2") (pintype "bidirectional"))
      (node (ref "B19") (pin "F2") (pinfunction "OUT_F2") (pintype "output"))
    )
    (net (code "8") (name "I_AC00") (class "Default")
      (node (ref "A03") (pin "B1") (pinfunction "P$2_B1") (pintype "bidirectional"))
      (node (ref "B03") (pin "B1") (pinfunction "P$2_B1") (pintype "bidirectional"))
      (node (ref "B16") (pin "D2") (pinfunction "OUT_D2") (pintype "output"))
    )
    (net (code "9") (name "I_AC01") (class "Default")
      (node (ref "A03") (pin "D1") (pinfunction "P$2_D1") (pintype "bidirectional"))
      (node (ref "B03") (pin "D1") (pinfunction "P$2_D1") (pintype "bidirectional"))
      (node (ref "B16") (pin "F2") (pinfunction "OUT_F2") (pintype "output"))
    )
    (net (code "10") (name "I_AC02") (class "Default")
      (node (ref "A03") (pin "E1") (pinfunction "P$2_E1") (pintype "bidirectional"))
      (node (ref "B03") (pin "E1") (pinfunction "P$2_E1") (pintype "bidirectional"))
      (node (ref "B16") (pin "J2") (pinfunction "OUT_J2") (pintype "output"))
    )
    (net (code "11") (name "I_AC03") (class "Default")
      (node (ref "A03") (pin "H1") (pinfunction "P$2_H1") (pintype "bidirectional"))
      (node (ref "B03") (pin "H1") (pinfunction "P$2_H1") (pintype "bidirectional"))
      (node (ref "B16") (pin "L2") (pinfunction "OUT_L2") (pintype "output"))
    )
    (net (code "12") (name "I_AC04") (class "Default")
      (node (ref "A03") (pin "J1") (pinfunction "P$2_J1") (pintype "bidirectional"))
      (node (ref "B03") (pin "J1") (pinfunction "P$2_J1") (pintype "bidirectional"))
      (node (ref "B16") (pin "N2") (pinfunction "OUT_N2") (pintype "output"))
    )
    (net (code "13") (name "I_AC05") (class "Default")
      (node (ref "A03") (pin "L1") (pinfunction "P$2_L1") (pintype "bidirectional"))
      (node (ref "B03") (pin "L1") (pinfunction "P$2_L1") (pintype "bidirectional"))
      (node (ref "B16") (pin "R2") (pinfunction "OUT_R2") (pintype "output"))
    )
    (net (code "14") (name "I_AC06") (class "Default")
      (node (ref "A03") (pin "M1") (pinfunction "P$2_M1") (pintype "bidirectional"))
      (node (ref "B03") (pin "M1") (pinfunction "P$2_M1") (pintype "bidirectional"))
      (node (ref "B17") (pin "D2") (pinfunction "OUT_D2") (pintype "output"))
    )
    (net (code "15") (name "I_AC07") (class "Default")
      (node (ref "A03") (pin "P1") (pinfunction "P$2_P1") (pintype "bidirectional"))
      (node (ref "B03") (pin "P1") (pinfunction "P$2_P1") (pintype "bidirectional"))
      (node (ref "B17") (pin "F2") (pinfunction "OUT_F2") (pintype "output"))
    )
    (net (code "16") (name "I_AC08") (class "Default")
      (node (ref "A03") (pin "S1") (pinfunction "P$2_S1") (pintype "bidirectional"))
      (node (ref "B03") (pin "S1") (pinfunction "P$2_S1") (pintype "bidirectional"))
      (node (ref "B17") (pin "J2") (pinfunction "OUT_J2") (pintype "output"))
    )
    (net (code "17") (name "I_AC09") (class "Default")
      (node (ref "A03") (pin "D2") (pinfunction "P$2_D2") (pintype "bidirectional"))
      (node (ref "B03") (pin "D2") (pinfunction "P$2_D2") (pintype "bidirectional"))
      (node (ref "B17") (pin "L2") (pinfunction "OUT_L2") (pintype "output"))
    )
    (net (code "18") (name "I_AC10") (class "Default")
      (node (ref "A03") (pin "E2") (pinfunction "P$2_E2") (pintype "bidirectional"))
      (node (ref "B03") (pin "E2") (pinfunction "P$2_E2") (pintype "bidirectional"))
      (node (ref "B17") (pin "N2") (pinfunction "OUT_N2") (pintype "output"))
    )
    (net (code "19") (name "I_AC11") (class "Default")
      (node (ref "A03") (pin "H2") (pinfunction "P$2_H2") (pintype "bidirectional"))
      (node (ref "B03") (pin "H2") (pinfunction "P$2_H2") (pintype "bidirectional"))
      (node (ref "B17") (pin "R2") (pinfunction "OUT_R2") (pintype "output"))
    )
    (net (code "20") (name "I_ACCEPT") (class "Default")
      (node (ref "A04") (pin "S2") (pinfunction "P$2_S2") (pintype "bidirectional"))
      (node (ref "B04") (pin "S2") (pinfunction "P$2_S2") (pintype "bidirectional"))
      (node (ref "B07") (pin "S2") (pinfunction "CATHODE_S2") (pintype "passive"))
      (node (ref "B15") (pin "H2") (pinfunction "IN2_H2") (pintype "input"))
    )
    (net (code "21") (name "I_ACCLR") (class "Default")
      (node (ref "A03") (pin "P2") (pinfunction "P$2_P2") (pintype "bidirectional"))
      (node (ref "B03") (pin "P2") (pinfunction "P$2_P2") (pintype "bidirectional"))
      (node (ref "B18") (pin "J2") (pinfunction "OUT_J2") (pintype "output"))
    )
    (net (code "22") (name "I_ADD00") (class "Default")
      (node (ref "A04") (pin "B1") (pinfunction "P$2_B1") (pintype "bidirectional"))
      (node (ref "B04") (pin "B1") (pinfunction "P$2_B1") (pintype "bidirectional"))
      (node (ref "B20") (pin "D2") (pinfunction "OUT_D2") (pintype "output"))
    )
    (net (code "23") (name "I_ADD01") (class "Default")
      (node (ref "A04") (pin "D1") (pinfunction "P$2_D1") (pintype "bidirectional"))
      (node (ref "B04") (pin "D1") (pinfunction "P$2_D1") (pintype "bidirectional"))
      (node (ref "B20") (pin "F2") (pinfunction "OUT_F2") (pintype "output"))
    )
    (net (code "24") (name "I_ADD02") (class "Default")
      (node (ref "A04") (pin "E1") (pinfunction "P$2_E1") (pintype "bidirectional"))
      (node (ref "B04") (pin "E1") (pinfunction "P$2_E1") (pintype "bidirectional"))
      (node (ref "B20") (pin "J2") (pinfunction "OUT_J2") (pintype "output"))
    )
    (net (code "25") (name "I_ADD03") (class "Default")
      (node (ref "A04") (pin "H1") (pinfunction "P$2_H1") (pintype "bidirectional"))
      (node (ref "B04") (pin "H1") (pinfunction "P$2_H1") (pintype "bidirectional"))
      (node (ref "B20") (pin "L2") (pinfunction "OUT_L2") (pintype "output"))
    )
    (net (code "26") (name "I_ADD04") (class "Default")
      (node (ref "A04") (pin "J1") (pinfunction "P$2_J1") (pintype "bidirectional"))
      (node (ref "B04") (pin "J1") (pinfunction "P$2_J1") (pintype "bidirectional"))
      (node (ref "B20") (pin "N2") (pinfunction "OUT_N2") (pintype "output"))
    )
    (net (code "27") (name "I_ADD05") (class "Default")
      (node (ref "A04") (pin "L1") (pinfunction "P$2_L1") (pintype "bidirectional"))
      (node (ref "B04") (pin "L1") (pinfunction "P$2_L1") (pintype "bidirectional"))
      (node (ref "B20") (pin "R2") (pinfunction "OUT_R2") (pintype "output"))
    )
    (net (code "28") (name "I_ADD06") (class "Default")
      (node (ref "A04") (pin "M1") (pinfunction "P$2_M1") (pintype "bidirectional"))
      (node (ref "B04") (pin "M1") (pinfunction "P$2_M1") (pintype "bidirectional"))
      (node (ref "B21") (pin "D2") (pinfunction "OUT_D2") (pintype "output"))
    )
    (net (code "29") (name "I_ADD07") (class "Default")
      (node (ref "A04") (pin "P1") (pinfunction "P$2_P1") (pintype "bidirectional"))
      (node (ref "B04") (pin "P1") (pinfunction "P$2_P1") (pintype "bidirectional"))
      (node (ref "B21") (pin "F2") (pinfunction "OUT_F2") (pintype "output"))
    )
    (net (code "30") (name "I_ADD08") (class "Default")
      (node (ref "A04") (pin "S1") (pinfunction "P$2_S1") (pintype "bidirectional"))
      (node (ref "B04") (pin "S1") (pinfunction "P$2_S1") (pintype "bidirectional"))
      (node (ref "B21") (pin "J2") (pinfunction "OUT_J2") (pintype "output"))
    )
    (net (code "31") (name "I_ADD09") (class "Default")
      (node (ref "A04") (pin "D2") (pinfunction "P$2_D2") (pintype "bidirectional"))
      (node (ref "B04") (pin "D2") (pinfunction "P$2_D2") (pintype "bidirectional"))
      (node (ref "B21") (pin "L2") (pinfunction "OUT_L2") (pintype "output"))
    )
    (net (code "32") (name "I_ADD10") (class "Default")
      (node (ref "A04") (pin "E2") (pinfunction "P$2_E2") (pintype "bidirectional"))
      (node (ref "B04") (pin "E2") (pinfunction "P$2_E2") (pintype "bidirectional"))
      (node (ref "B21") (pin "N2") (pinfunction "OUT_N2") (pintype "output"))
    )
    (net (code "33") (name "I_ADD11") (class "Default")
      (node (ref "A04") (pin "H2") (pinfunction "P$2_H2") (pintype "bidirectional"))
      (node (ref "B04") (pin "H2") (pinfunction "P$2_H2") (pintype "bidirectional"))
      (node (ref "B21") (pin "R2") (pinfunction "OUT_R2") (pintype "output"))
    )
    (net (code "34") (name "I_BAC00") (class "Default")
      (node (ref "A01") (pin "B1") (pinfunction "P$2_B1") (pintype "bidirectional"))
      (node (ref "B01") (pin "B1") (pinfunction "P$2_B1") (pintype "bidirectional"))
      (node (ref "B07") (pin "B1") (pinfunction "CATHODE_B1") (pintype "passive"))
      (node (ref "B10") (pin "H2") (pinfunction "IN2_H2") (pintype "input"))
    )
    (net (code "35") (name "I_BAC01") (class "Default")
      (node (ref "A01") (pin "D1") (pinfunction "P$2_D1") (pintype "bidirectional"))
      (node (ref "B01") (pin "D1") (pinfunction "P$2_D1") (pintype "bidirectional"))
      (node (ref "B07") (pin "D1") (pinfunction "CATHODE_D1") (pintype "passive"))
      (node (ref "B10") (pin "N2") (pinfunction "IN2_N2") (pintype "input"))
    )
    (net (code "36") (name "I_BAC02") (class "Default")
      (node (ref "A01") (pin "E1") (pinfunction "P$2_E1") (pintype "bidirectional"))
      (node (ref "B01") (pin "E1") (pinfunction "P$2_E1") (pintype "bidirectional"))
      (node (ref "B07") (pin "E1") (pinfunction "CATHODE_E1") (pintype "passive"))
      (node (ref "B10") (pin "U2") (pinfunction "IN2_U2") (pintype "input"))
    )
    (net (code "37") (name "I_BAC03") (class "Default")
      (node (ref "A01") (pin "H1") (pinfunction "P$2_H1") (pintype "bidirectional"))
      (node (ref "B01") (pin "H1") (pinfunction "P$2_H1") (pintype "bidirectional"))
      (node (ref "B07") (pin "H1") (pinfunction "CATHODE_H1") (pintype "passive"))
      (node (ref "B11") (pin "H2") (pinfunction "IN2_H2") (pintype "input"))
    )
    (net (code "38") (name "I_BAC04") (class "Default")
      (node (ref "A01") (pin "J1") (pinfunction "P$2_J1") (pintype "bidirectional"))
      (node (ref "B01") (pin "J1") (pinfunction "P$2_J1") (pintype "bidirectional"))
      (node (ref "B07") (pin "J1") (pinfunction "CATHODE_J1") (pintype "passive"))
      (node (ref "B11") (pin "N2") (pinfunction "IN2_N2") (pintype "input"))
    )
    (net (code "39") (name "I_BAC05") (class "Default")
      (node (ref "A01") (pin "L1") (pinfunction "P$2_L1") (pintype "bidirectional"))
      (node (ref "B01") (pin "L1") (pinfunction "P$2_L1") (pintype "bidirectional"))
      (node (ref "B07") (pin "L1") (pinfunction "CATHODE_L1") (pintype "passive"))
      (node (ref "B11") (pin "U2") (pinfunction "IN2_U2") (pintype "input"))
    )
    (net (code "40") (name "I_BAC06") (class "Default")
      (node (ref "A01") (pin "M1") (pinfunction "P$2_M1") (pintype "bidirectional"))
      (node (ref "B01") (pin "M1") (pinfunction "P$2_M1") (pintype "bidirectional"))
      (node (ref "B07") (pin "M1") (pinfunction "CATHODE_M1") (pintype "passive"))
      (node (ref "B12") (pin "H2") (pinfunction "IN2_H2") (pintype "input"))
    )
    (net (code "41") (name "I_BAC07") (class "Default")
      (node (ref "A01") (pin "P1") (pinfunction "P$2_P1") (pintype "bidirectional"))
      (node (ref "B01") (pin "P1") (pinfunction "P$2_P1") (pintype "bidirectional"))
      (node (ref "B07") (pin "P1") (pinfunction "CATHODE_P1") (pintype "passive"))
      (node (ref "B12") (pin "N2") (pinfunction "IN2_N2") (pintype "input"))
    )
    (net (code "42") (name "I_BAC08") (class "Default")
      (node (ref "A01") (pin "S1") (pinfunction "P$2_S1") (pintype "bidirectional"))
      (node (ref "B01") (pin "S1") (pinfunction "P$2_S1") (pintype "bidirectional"))
      (node (ref "B07") (pin "S1") (pinfunction "CATHODE_S1") (pintype "passive"))
      (node (ref "B12") (pin "U2") (pinfunction "IN2_U2") (pintype "input"))
    )
    (net (code "43") (name "I_BAC09") (class "Default")
      (node (ref "A01") (pin "D2") (pinfunction "P$2_D2") (pintype "bidirectional"))
      (node (ref "B01") (pin "D2") (pinfunction "P$2_D2") (pintype "bidirectional"))
      (node (ref "B07") (pin "D2") (pinfunction "CATHODE_D2") (pintype "passive"))
      (node (ref "B13") (pin "H2") (pinfunction "IN2_H2") (pintype "input"))
    )
    (net (code "44") (name "I_BAC10") (class "Default")
      (node (ref "A01") (pin "E2") (pinfunction "P$2_E2") (pintype "bidirectional"))
      (node (ref "B01") (pin "E2") (pinfunction "P$2_E2") (pintype "bidirectional"))
      (node (ref "B07") (pin "E2") (pinfunction "CATHODE_E2") (pintype "passive"))
      (node (ref "B13") (pin "N2") (pinfunction "IN2_N2") (pintype "input"))
    )
    (net (code "45") (name "I_BAC11") (class "Default")
      (node (ref "A01") (pin "H2") (pinfunction "P$2_H2") (pintype "bidirectional"))
      (node (ref "B01") (pin "H2") (pinfunction "P$2_H2") (pintype "bidirectional"))
      (node (ref "B07") (pin "H2") (pinfunction "CATHODE_H2") (pintype "passive"))
      (node (ref "B13") (pin "U2") (pinfunction "IN2_U2") (pintype "input"))
    )
    (net (code "46") (name "I_BREAK") (class "Default")
      (node (ref "A04") (pin "P2") (pinfunction "P$2_P2") (pintype "bidirectional"))
      (node (ref "B04") (pin "P2") (pinfunction "P$2_P2") (pintype "bidirectional"))
      (node (ref "B07") (pin "P2") (pinfunction "CATHODE_P2") (pintype "passive"))
      (node (ref "B14") (pin "U2") (pinfunction "IN2_U2") (pintype "input"))
      (node (ref "B22") (pin "V2") (pinfunction "P$1_V2") (pintype "input"))
      (node (ref "B23") (pin "V2") (pinfunction "P$1_V2") (pintype "input"))
    )
    (net (code "47") (name "I_BRKRQ") (class "Default")
      (node (ref "A04") (pin "K2") (pinfunction "P$2_K2") (pintype "bidirectional"))
      (node (ref "B04") (pin "K2") (pinfunction "P$2_K2") (pintype "bidirectional"))
      (node (ref "B18") (pin "N2") (pinfunction "OUT_N2") (pintype "output"))
    )
    (net (code "48") (name "I_CAINCR") (class "Default")
      (node (ref "A05") (pin "M2") (pinfunction "P$2_M2") (pintype "bidirectional"))
      (node (ref "B05") (pin "M2") (pinfunction "P$2_M2") (pintype "bidirectional"))
      (node (ref "B19") (pin "J2") (pinfunction "OUT_J2") (pintype "output"))
    )
    (net (code "49") (name "I_DATA00") (class "Default")
      (node (ref "A05") (pin "B1") (pinfunction "P$2_B1") (pintype "bidirectional"))
      (node (ref "B05") (pin "B1") (pinfunction "P$2_B1") (pintype "bidirectional"))
      (node (ref "B22") (pin "D2") (pinfunction "OUT_D2") (pintype "output"))
    )
    (net (code "50") (name "I_DATA01") (class "Default")
      (node (ref "A05") (pin "D1") (pinfunction "P$2_D1") (pintype "bidirectional"))
      (node (ref "B05") (pin "D1") (pinfunction "P$2_D1") (pintype "bidirectional"))
      (node (ref "B22") (pin "F2") (pinfunction "OUT_F2") (pintype "output"))
    )
    (net (code "51") (name "I_DATA02") (class "Default")
      (node (ref "A05") (pin "E1") (pinfunction "P$2_E1") (pintype "bidirectional"))
      (node (ref "B05") (pin "E1") (pinfunction "P$2_E1") (pintype "bidirectional"))
      (node (ref "B22") (pin "J2") (pinfunction "OUT_J2") (pintype "output"))
    )
    (net (code "52") (name "I_DATA03") (class "Default")
      (node (ref "A05") (pin "H1") (pinfunction "P$2_H1") (pintype "bidirectional"))
      (node (ref "B05") (pin "H1") (pinfunction "P$2_H1") (pintype "bidirectional"))
      (node (ref "B22") (pin "L2") (pinfunction "OUT_L2") (pintype "output"))
    )
    (net (code "53") (name "I_DATA04") (class "Default")
      (node (ref "A05") (pin "J1") (pinfunction "P$2_J1") (pintype "bidirectional"))
      (node (ref "B05") (pin "J1") (pinfunction "P$2_J1") (pintype "bidirectional"))
      (node (ref "B22") (pin "N2") (pinfunction "OUT_N2") (pintype "output"))
    )
    (net (code "54") (name "I_DATA05") (class "Default")
      (node (ref "A05") (pin "L1") (pinfunction "P$2_L1") (pintype "bidirectional"))
      (node (ref "B05") (pin "L1") (pinfunction "P$2_L1") (pintype "bidirectional"))
      (node (ref "B22") (pin "R2") (pinfunction "OUT_R2") (pintype "output"))
    )
    (net (code "55") (name "I_DATA06") (class "Default")
      (node (ref "A05") (pin "M1") (pinfunction "P$2_M1") (pintype "bidirectional"))
      (node (ref "B05") (pin "M1") (pinfunction "P$2_M1") (pintype "bidirectional"))
      (node (ref "B23") (pin "D2") (pinfunction "OUT_D2") (pintype "output"))
    )
    (net (code "56") (name "I_DATA07") (class "Default")
      (node (ref "A05") (pin "P1") (pinfunction "P$2_P1") (pintype "bidirectional"))
      (node (ref "B05") (pin "P1") (pinfunction "P$2_P1") (pintype "bidirectional"))
      (node (ref "B23") (pin "F2") (pinfunction "OUT_F2") (pintype "output"))
    )
    (net (code "57") (name "I_DATA08") (class "Default")
      (node (ref "A05") (pin "S1") (pinfunction "P$2_S1") (pintype "bidirectional"))
      (node (ref "B05") (pin "S1") (pinfunction "P$2_S1") (pintype "bidirectional"))
      (node (ref "B23") (pin "J2") (pinfunction "OUT_J2") (pintype "output"))
    )
    (net (code "58") (name "I_DATA09") (class "Default")
      (node (ref "A05") (pin "D2") (pinfunction "P$2_D2") (pintype "bidirectional"))
      (node (ref "B05") (pin "D2") (pinfunction "P$2_D2") (pintype "bidirectional"))
      (node (ref "B23") (pin "L2") (pinfunction "OUT_L2") (pintype "output"))
    )
    (net (code "59") (name "I_DATA10") (class "Default")
      (node (ref "A05") (pin "E2") (pinfunction "P$2_E2") (pintype "bidirectional"))
      (node (ref "B05") (pin "E2") (pinfunction "P$2_E2") (pintype "bidirectional"))
      (node (ref "B23") (pin "N2") (pinfunction "OUT_N2") (pintype "output"))
    )
    (net (code "60") (name "I_DATA11") (class "Default")
      (node (ref "A05") (pin "H2") (pinfunction "P$2_H2") (pintype "bidirectional"))
      (node (ref "B05") (pin "H2") (pinfunction "P$2_H2") (pintype "bidirectional"))
      (node (ref "B23") (pin "R2") (pinfunction "OUT_R2") (pintype "output"))
    )
    (net (code "61") (name "I_DATAIN") (class "Default")
      (node (ref "A04") (pin "M2") (pinfunction "P$2_M2") (pintype "bidirectional"))
      (node (ref "B04") (pin "M2") (pinfunction "P$2_M2") (pintype "bidirectional"))
      (node (ref "B18") (pin "R2") (pinfunction "OUT_R2") (pintype "output"))
    )
    (net (code "62") (name "I_EXTA0") (class "Default")
      (node (ref "A05") (pin "V2") (pinfunction "P$2_V2") (pintype "bidirectional"))
      (node (ref "B05") (pin "V2") (pinfunction "P$2_V2") (pintype "bidirectional"))
      (node (ref "B19") (pin "R2") (pinfunction "OUT_R2") (pintype "output"))
    )
    (net (code "63") (name "I_EXTA1") (class "Default")
      (node (ref "A05") (pin "T2") (pinfunction "P$2_T2") (pintype "bidirectional"))
      (node (ref "B05") (pin "T2") (pinfunction "P$2_T2") (pintype "bidirectional"))
      (node (ref "B19") (pin "N2") (pinfunction "OUT_N2") (pintype "output"))
    )
    (net (code "64") (name "I_EXTA2") (class "Default")
      (node (ref "A05") (pin "S2") (pinfunction "P$2_S2") (pintype "bidirectional"))
      (node (ref "B05") (pin "S2") (pinfunction "P$2_S2") (pintype "bidirectional"))
      (node (ref "B19") (pin "L2") (pinfunction "OUT_L2") (pintype "output"))
    )
    (net (code "65") (name "I_INIT") (class "Default")
      (node (ref "A01") (pin "V2") (pinfunction "P$2_V2") (pintype "bidirectional"))
      (node (ref "A04") (pin "V2") (pinfunction "P$2_V2") (pintype "bidirectional"))
      (node (ref "B01") (pin "V2") (pinfunction "P$2_V2") (pintype "bidirectional"))
      (node (ref "B04") (pin "V2") (pinfunction "P$2_V2") (pintype "bidirectional"))
      (node (ref "B06") (pin "N1") (pinfunction "IN_N1") (pintype "input"))
    )
    (net (code "66") (name "I_IOP1") (class "Default")
      (node (ref "A01") (pin "K2") (pinfunction "P$2_K2") (pintype "bidirectional"))
      (node (ref "B01") (pin "K2") (pinfunction "P$2_K2") (pintype "bidirectional"))
      (node (ref "B06") (pin "A1") (pinfunction "IN1_A1") (pintype "input"))
    )
    (net (code "67") (name "I_IOP2") (class "Default")
      (node (ref "A01") (pin "M2") (pinfunction "P$2_M2") (pintype "bidirectional"))
      (node (ref "B01") (pin "M2") (pinfunction "P$2_M2") (pintype "bidirectional"))
      (node (ref "B06") (pin "D1") (pinfunction "IN_D1") (pintype "input"))
    )
    (net (code "68") (name "I_IOP4") (class "Default")
      (node (ref "A01") (pin "P2") (pinfunction "P$2_P2") (pintype "bidirectional"))
      (node (ref "B01") (pin "P2") (pinfunction "P$2_P2") (pintype "bidirectional"))
      (node (ref "B06") (pin "F1") (pinfunction "IN_F1") (pintype "input"))
    )
    (net (code "69") (name "I_IRQ") (class "Default")
      (node (ref "A03") (pin "M2") (pinfunction "P$2_M2") (pintype "bidirectional"))
      (node (ref "B03") (pin "M2") (pinfunction "P$2_M2") (pintype "bidirectional"))
      (node (ref "B18") (pin "F2") (pinfunction "OUT_F2") (pintype "output"))
    )
    (net (code "70") (name "I_LINE") (class "Default")
      (node (ref "A03") (pin "V2") (pinfunction "P$2_V2") (pintype "bidirectional"))
      (node (ref "B03") (pin "V2") (pinfunction "P$2_V2") (pintype "bidirectional"))
      (node (ref "B18") (pin "L2") (pinfunction "OUT_L2") (pintype "output"))
    )
    (net (code "71") (name "I_MB00") (class "Default")
      (node (ref "A02") (pin "B1") (pinfunction "P$2_B1") (pintype "bidirectional"))
      (node (ref "A06") (pin "B1") (pinfunction "CATHODE_B1") (pintype "passive"))
      (node (ref "A07") (pin "H2") (pinfunction "IN2_H2") (pintype "input"))
      (node (ref "B02") (pin "B1") (pinfunction "P$2_B1") (pintype "bidirectional"))
    )
    (net (code "72") (name "I_MB01") (class "Default")
      (node (ref "A02") (pin "D1") (pinfunction "P$2_D1") (pintype "bidirectional"))
      (node (ref "A06") (pin "D1") (pinfunction "CATHODE_D1") (pintype "passive"))
      (node (ref "A07") (pin "N2") (pinfunction "IN2_N2") (pintype "input"))
      (node (ref "B02") (pin "D1") (pinfunction "P$2_D1") (pintype "bidirectional"))
    )
    (net (code "73") (name "I_MB02") (class "Default")
      (node (ref "A02") (pin "E1") (pinfunction "P$2_E1") (pintype "bidirectional"))
      (node (ref "A06") (pin "E1") (pinfunction "CATHODE_E1") (pintype "passive"))
      (node (ref "A07") (pin "U2") (pinfunction "IN2_U2") (pintype "input"))
      (node (ref "B02") (pin "E1") (pinfunction "P$2_E1") (pintype "bidirectional"))
    )
    (net (code "74") (name "I_MB03") (class "Default")
      (node (ref "A02") (pin "J1") (pinfunction "P$2_J1") (pintype "bidirectional"))
      (node (ref "A06") (pin "J1") (pinfunction "CATHODE_J1") (pintype "passive"))
      (node (ref "A08") (pin "N2") (pinfunction "IN2_N2") (pintype "input"))
      (node (ref "B02") (pin "J1") (pinfunction "P$2_J1") (pintype "bidirectional"))
    )
    (net (code "75") (name "I_MB04") (class "Default")
      (node (ref "A02") (pin "M1") (pinfunction "P$2_M1") (pintype "bidirectional"))
      (node (ref "A06") (pin "M1") (pinfunction "CATHODE_M1") (pintype "passive"))
      (node (ref "A09") (pin "H2") (pinfunction "IN2_H2") (pintype "input"))
      (node (ref "B02") (pin "M1") (pinfunction "P$2_M1") (pintype "bidirectional"))
    )
    (net (code "76") (name "I_MB05") (class "Default")
      (node (ref "A02") (pin "S1") (pinfunction "P$2_S1") (pintype "bidirectional"))
      (node (ref "A06") (pin "S1") (pinfunction "CATHODE_S1") (pintype "passive"))
      (node (ref "A09") (pin "U2") (pinfunction "IN2_U2") (pintype "input"))
      (node (ref "B02") (pin "S1") (pinfunction "P$2_S1") (pintype "bidirectional"))
    )
    (net (code "77") (name "I_MB06") (class "Default")
      (node (ref "A02") (pin "E2") (pinfunction "P$2_E2") (pintype "bidirectional"))
      (node (ref "A06") (pin "E2") (pinfunction "CATHODE_E2") (pintype "passive"))
      (node (ref "A10") (pin "N2") (pinfunction "IN2_N2") (pintype "input"))
      (node (ref "B02") (pin "E2") (pinfunction "P$2_E2") (pintype "bidirectional"))
    )
    (net (code "78") (name "I_MB07") (class "Default")
      (node (ref "A02") (pin "K2") (pinfunction "P$2_K2") (pintype "bidirectional"))
      (node (ref "A06") (pin "K2") (pinfunction "CATHODE_K2") (pintype "passive"))
      (node (ref "A11") (pin "H2") (pinfunction "IN2_H2") (pintype "input"))
      (node (ref "B02") (pin "K2") (pinfunction "P$2_K2") (pintype "bidirectional"))
    )
    (net (code "79") (name "I_MB08") (class "Default")
      (node (ref "A02") (pin "P2") (pinfunction "P$2_P2") (pintype "bidirectional"))
      (node (ref "A06") (pin "P2") (pinfunction "CATHODE_P2") (pintype "passive"))
      (node (ref "A11") (pin "U2") (pinfunction "IN2_U2") (pintype "input"))
      (node (ref "B02") (pin "P2") (pinfunction "P$2_P2") (pintype "bidirectional"))
    )
    (net (code "80") (name "I_MB09") (class "Default")
      (node (ref "A02") (pin "S2") (pinfunction "P$2_S2") (pintype "bidirectional"))
      (node (ref "A06") (pin "S2") (pinfunction "CATHODE_S2") (pintype "passive"))
      (node (ref "A12") (pin "H2") (pinfunction "IN2_H2") (pintype "input"))
      (node (ref "B02") (pin "S2") (pinfunction "P$2_S2") (pintype "bidirectional"))
    )
    (net (code "81") (name "I_MB10") (class "Default")
      (node (ref "A02") (pin "T2") (pinfunction "P$2_T2") (pintype "bidirectional"))
      (node (ref "A06") (pin "T2") (pinfunction "CATHODE_T2") (pintype "passive"))
      (node (ref "A12") (pin "N2") (pinfunction "IN2_N2") (pintype "input"))
      (node (ref "B02") (pin "T2") (pinfunction "P$2_T2") (pintype "bidirectional"))
    )
    (net (code "82") (name "I_MB11") (class "Default")
      (node (ref "A02") (pin "V2") (pinfunction "P$2_V2") (pintype "bidirectional"))
      (node (ref "A06") (pin "V2") (pinfunction "CATHODE_V2") (pintype "passive"))
      (node (ref "A12") (pin "U2") (pinfunction "IN2_U2") (pintype "input"))
      (node (ref "B02") (pin "V2") (pinfunction "P$2_V2") (pintype "bidirectional"))
    )
    (net (code "83") (name "I_MBINCR") (class "Default")
      (node (ref "A04") (pin "T2") (pinfunction "P$2_T2") (pintype "bidirectional"))
      (node (ref "B04") (pin "T2") (pinfunction "P$2_T2") (pintype "bidirectional"))
      (node (ref "B19") (pin "D2") (pinfunction "OUT_D2") (pintype "output"))
    )
    (net (code "84") (name "I_RUN") (class "Default")
      (node (ref "A03") (pin "S2") (pinfunction "P$2_S2") (pintype "bidirectional"))
      (node (ref "B03") (pin "S2") (pinfunction "P$2_S2") (pintype "bidirectional"))
      (node (ref "B07") (pin "K2") (pinfunction "CATHODE_K2") (pintype "passive"))
      (node (ref "B14") (pin "H2") (pinfunction "IN2_H2") (pintype "input"))
    )
    (net (code "85") (name "I_SKIP") (class "Default")
      (node (ref "A03") (pin "K2") (pinfunction "P$2_K2") (pintype "bidirectional"))
      (node (ref "B03") (pin "K2") (pinfunction "P$2_K2") (pintype "bidirectional"))
      (node (ref "B18") (pin "D2") (pinfunction "OUT_D2") (pintype "output"))
    )
    (net (code "86") (name "I_TS1") (class "Default")
      (node (ref "A01") (pin "T2") (pinfunction "P$2_T2") (pintype "bidirectional"))
      (node (ref "B01") (pin "T2") (pinfunction "P$2_T2") (pintype "bidirectional"))
      (node (ref "B06") (pin "L1") (pinfunction "IN_L1") (pintype "input"))
    )
    (net (code "87") (name "I_TS3") (class "Default")
      (node (ref "A01") (pin "S2") (pinfunction "P$2_S2") (pintype "bidirectional"))
      (node (ref "B01") (pin "S2") (pinfunction "P$2_S2") (pintype "bidirectional"))
      (node (ref "B06") (pin "J1") (pinfunction "IN_J1") (pintype "input"))
    )
    (net (code "88") (name "I_TT_INST") (class "Default")
      (node (ref "A03") (pin "T2") (pinfunction "P$2_T2") (pintype "bidirectional"))
      (node (ref "B03") (pin "T2") (pinfunction "P$2_T2") (pintype "bidirectional"))
      (node (ref "B07") (pin "M2") (pinfunction "CATHODE_M2") (pintype "passive"))
      (node (ref "B14") (pin "N2") (pinfunction "IN2_N2") (pintype "input"))
    )
    (net (code "89") (name "I_WCOV") (class "Default")
      (node (ref "A05") (pin "P2") (pinfunction "P$2_P2") (pintype "bidirectional"))
      (node (ref "B05") (pin "P2") (pinfunction "P$2_P2") (pintype "bidirectional"))
      (node (ref "B07") (pin "T2") (pinfunction "CATHODE_T2") (pintype "passive"))
      (node (ref "B15") (pin "N2") (pinfunction "IN2_N2") (pintype "input"))
    )
    (net (code "90") (name "Net-(B06A-OUT)") (class "Default")
      (node (ref "B06") (pin "B1") (pinfunction "OUT_B1") (pintype "output"))
      (node (ref "B08") (pin "H2") (pinfunction "IN2_H2") (pintype "input"))
    )
    (net (code "91") (name "Net-(B06B-OUT)") (class "Default")
      (node (ref "B06") (pin "E1") (pinfunction "OUT_E1") (pintype "output"))
      (node (ref "B08") (pin "N2") (pinfunction "IN2_N2") (pintype "input"))
    )
    (net (code "92") (name "Net-(B06F-OUT)") (class "Default")
      (node (ref "B06") (pin "H1") (pinfunction "OUT_H1") (pintype "output"))
      (node (ref "B08") (pin "U2") (pinfunction "IN2_U2") (pintype "input"))
    )
    (net (code "93") (name "Net-(B06H-OUT)") (class "Default")
      (node (ref "B06") (pin "K1") (pinfunction "OUT_K1") (pintype "output"))
      (node (ref "B09") (pin "H2") (pinfunction "IN2_H2") (pintype "input"))
    )
    (net (code "94") (name "Net-(B06J-OUT)") (class "Default")
      (node (ref "B06") (pin "M1") (pinfunction "OUT_M1") (pintype "output"))
      (node (ref "B09") (pin "N2") (pinfunction "IN2_N2") (pintype "input"))
    )
    (net (code "95") (name "Net-(B06L-OUT)") (class "Default")
      (node (ref "B06") (pin "P1") (pinfunction "OUT_P1") (pintype "output"))
      (node (ref "B09") (pin "U2") (pinfunction "IN2_U2") (pintype "input"))
    )
    (net (code "96") (name "O_3CYCLE") (class "Default")
      (node (ref "A22") (pin "K2") (pinfunction "P$2_K2") (pintype "bidirectional"))
      (node (ref "B19") (pin "H2") (pinfunction "IN_H2") (pintype "input"))
    )
    (net (code "97") (name "O_AC00") (class "Default")
      (node (ref "A17") (pin "D2") (pinfunction "P$2_D2") (pintype "bidirectional"))
      (node (ref "B16") (pin "E2") (pinfunction "IN_E2") (pintype "input"))
    )
    (net (code "98") (name "O_AC01") (class "Default")
      (node (ref "A17") (pin "E2") (pinfunction "P$2_E2") (pintype "bidirectional"))
      (node (ref "B16") (pin "H2") (pinfunction "IN_H2") (pintype "input"))
    )
    (net (code "99") (name "O_AC02") (class "Default")
      (node (ref "A17") (pin "H2") (pinfunction "P$2_H2") (pintype "bidirectional"))
      (node (ref "B16") (pin "K2") (pinfunction "IN_K2") (pintype "input"))
    )
    (net (code "100") (name "O_AC03") (class "Default")
      (node (ref "A17") (pin "K2") (pinfunction "P$2_K2") (pintype "bidirectional"))
      (node (ref "B16") (pin "M2") (pinfunction "IN_M2") (pintype "input"))
    )
    (net (code "101") (name "O_AC04") (class "Default")
      (node (ref "A17") (pin "M2") (pinfunction "P$2_M2") (pintype "bidirectional"))
      (node (ref "B16") (pin "P2") (pinfunction "IN_P2") (pintype "input"))
    )
    (net (code "102") (name "O_AC05") (class "Default")
      (node (ref "A17") (pin "P2") (pinfunction "P$2_P2") (pintype "bidirectional"))
      (node (ref "B16") (pin "S2") (pinfunction "IN_S2") (pintype "input"))
    )
    (net (code "103") (name "O_AC06") (class "Default")
      (node (ref "A17") (pin "S2") (pinfunction "P$2_S2") (pintype "bidirectional"))
      (node (ref "B17") (pin "E2") (pinfunction "IN_E2") (pintype "input"))
    )
    (net (code "104") (name "O_AC07") (class "Default")
      (node (ref "A17") (pin "T2") (pinfunction "P$2_T2") (pintype "bidirectional"))
      (node (ref "B17") (pin "H2") (pinfunction "IN_H2") (pintype "input"))
    )
    (net (code "105") (name "O_AC08") (class "Default")
      (node (ref "A17") (pin "V2") (pinfunction "P$2_V2") (pintype "bidirectional"))
      (node (ref "B17") (pin "K2") (pinfunction "IN_K2") (pintype "input"))
    )
    (net (code "106") (name "O_AC09") (class "Default")
      (node (ref "A18") (pin "D2") (pinfunction "P$2_D2") (pintype "bidirectional"))
      (node (ref "B17") (pin "M2") (pinfunction "IN_M2") (pintype "input"))
    )
    (net (code "107") (name "O_AC10") (class "Default")
      (node (ref "A18") (pin "E2") (pinfunction "P$2_E2") (pintype "bidirectional"))
      (node (ref "B17") (pin "P2") (pinfunction "IN_P2") (pintype "input"))
    )
    (net (code "108") (name "O_AC11") (class "Default")
      (node (ref "A18") (pin "H2") (pinfunction "P$2_H2") (pintype "bidirectional"))
      (node (ref "B17") (pin "S2") (pinfunction "IN_S2") (pintype "input"))
    )
    (net (code "109") (name "O_ACCEPT") (class "Default")
      (node (ref "A20") (pin "S2") (pinfunction "P$2_S2") (pintype "bidirectional"))
      (node (ref "B15") (pin "D2") (pinfunction "OUT_D2") (pintype "output"))
    )
    (net (code "110") (name "O_ACCLR") (class "Default")
      (node (ref "A18") (pin "P2") (pinfunction "P$2_P2") (pintype "bidirectional"))
      (node (ref "B18") (pin "K2") (pinfunction "IN_K2") (pintype "input"))
    )
    (net (code "111") (name "O_ADD00") (class "Default")
      (node (ref "A19") (pin "D2") (pinfunction "P$2_D2") (pintype "bidirectional"))
      (node (ref "B20") (pin "E2") (pinfunction "IN_E2") (pintype "input"))
    )
    (net (code "112") (name "O_ADD01") (class "Default")
      (node (ref "A19") (pin "E2") (pinfunction "P$2_E2") (pintype "bidirectional"))
      (node (ref "B20") (pin "H2") (pinfunction "IN_H2") (pintype "input"))
    )
    (net (code "113") (name "O_ADD02") (class "Default")
      (node (ref "A19") (pin "H2") (pinfunction "P$2_H2") (pintype "bidirectional"))
      (node (ref "B20") (pin "K2") (pinfunction "IN_K2") (pintype "input"))
    )
    (net (code "114") (name "O_ADD03") (class "Default")
      (node (ref "A19") (pin "K2") (pinfunction "P$2_K2") (pintype "bidirectional"))
      (node (ref "B20") (pin "M2") (pinfunction "IN_M2") (pintype "input"))
    )
    (net (code "115") (name "O_ADD04") (class "Default")
      (node (ref "A19") (pin "M2") (pinfunction "P$2_M2") (pintype "bidirectional"))
      (node (ref "B20") (pin "P2") (pinfunction "IN_P2") (pintype "input"))
    )
    (net (code "116") (name "O_ADD05") (class "Default")
      (node (ref "A19") (pin "P2") (pinfunction "P$2_P2") (pintype "bidirectional"))
      (node (ref "B20") (pin "S2") (pinfunction "IN_S2") (pintype "input"))
    )
    (net (code "117") (name "O_ADD06") (class "Default")
      (node (ref "A19") (pin "S2") (pinfunction "P$2_S2") (pintype "bidirectional"))
      (node (ref "B21") (pin "E2") (pinfunction "IN_E2") (pintype "input"))
    )
    (net (code "118") (name "O_ADD07") (class "Default")
      (node (ref "A19") (pin "T2") (pinfunction "P$2_T2") (pintype "bidirectional"))
      (node (ref "B21") (pin "H2") (pinfunction "IN_H2") (pintype "input"))
    )
    (net (code "119") (name "O_ADD08") (class "Default")
      (node (ref "A19") (pin "V2") (pinfunction "P$2_V2") (pintype "bidirectional"))
      (node (ref "B21") (pin "K2") (pinfunction "IN_K2") (pintype "input"))
    )
    (net (code "120") (name "O_ADD09") (class "Default")
      (node (ref "A20") (pin "D2") (pinfunction "P$2_D2") (pintype "bidirectional"))
      (node (ref "B21") (pin "M2") (pinfunction "IN_M2") (pintype "input"))
    )
    (net (code "121") (name "O_ADD10") (class "Default")
      (node (ref "A20") (pin "E2") (pinfunction "P$2_E2") (pintype "bidirectional"))
      (node (ref "B21") (pin "P2") (pinfunction "IN_P2") (pintype "input"))
    )
    (net (code "122") (name "O_ADD11") (class "Default")
      (node (ref "A20") (pin "H2") (pinfunction "P$2_H2") (pintype "bidirectional"))
      (node (ref "B21") (pin "S2") (pinfunction "IN_S2") (pintype "input"))
    )
    (net (code "123") (name "O_BAC00") (class "Default")
      (node (ref "A13") (pin "D2") (pinfunction "P$2_D2") (pintype "bidirectional"))
      (node (ref "B10") (pin "D2") (pinfunction "OUT_D2") (pintype "output"))
    )
    (net (code "124") (name "O_BAC01") (class "Default")
      (node (ref "A13") (pin "E2") (pinfunction "P$2_E2") (pintype "bidirectional"))
      (node (ref "B10") (pin "K2") (pinfunction "OUT_K2") (pintype "output"))
    )
    (net (code "125") (name "O_BAC02") (class "Default")
      (node (ref "A13") (pin "H2") (pinfunction "P$2_H2") (pintype "bidirectional"))
      (node (ref "B10") (pin "S2") (pinfunction "OUT_S2") (pintype "output"))
    )
    (net (code "126") (name "O_BAC03") (class "Default")
      (node (ref "A13") (pin "K2") (pinfunction "P$2_K2") (pintype "bidirectional"))
      (node (ref "B11") (pin "D2") (pinfunction "OUT_D2") (pintype "output"))
    )
    (net (code "127") (name "O_BAC04") (class "Default")
      (node (ref "A13") (pin "M2") (pinfunction "P$2_M2") (pintype "bidirectional"))
      (node (ref "B11") (pin "K2") (pinfunction "OUT_K2") (pintype "output"))
    )
    (net (code "128") (name "O_BAC05") (class "Default")
      (node (ref "A13") (pin "P2") (pinfunction "P$2_P2") (pintype "bidirectional"))
      (node (ref "B11") (pin "S2") (pinfunction "OUT_S2") (pintype "output"))
    )
    (net (code "129") (name "O_BAC06") (class "Default")
      (node (ref "A13") (pin "S2") (pinfunction "P$2_S2") (pintype "bidirectional"))
      (node (ref "B12") (pin "D2") (pinfunction "OUT_D2") (pintype "output"))
    )
    (net (code "130") (name "O_BAC07") (class "Default")
      (node (ref "A13") (pin "T2") (pinfunction "P$2_T2") (pintype "bidirectional"))
      (node (ref "B12") (pin "K2") (pinfunction "OUT_K2") (pintype "output"))
    )
    (net (code "131") (name "O_BAC08") (class "Default")
      (node (ref "A13") (pin "V2") (pinfunction "P$2_V2") (pintype "bidirectional"))
      (node (ref "B12") (pin "S2") (pinfunction "OUT_S2") (pintype "output"))
    )
    (net (code "132") (name "O_BAC09") (class "Default")
      (node (ref "A14") (pin "D2") (pinfunction "P$2_D2") (pintype "bidirectional"))
      (node (ref "B13") (pin "D2") (pinfunction "OUT_D2") (pintype "output"))
    )
    (net (code "133") (name "O_BAC10") (class "Default")
      (node (ref "A14") (pin "E2") (pinfunction "P$2_E2") (pintype "bidirectional"))
      (node (ref "B13") (pin "K2") (pinfunction "OUT_K2") (pintype "output"))
    )
    (net (code "134") (name "O_BAC11") (class "Default")
      (node (ref "A14") (pin "H2") (pinfunction "P$2_H2") (pintype "bidirectional"))
      (node (ref "B13") (pin "S2") (pinfunction "OUT_S2") (pintype "output"))
    )
    (net (code "135") (name "O_BREAK") (class "Default")
      (node (ref "A20") (pin "P2") (pinfunction "P$2_P2") (pintype "bidirectional"))
      (node (ref "B14") (pin "S2") (pinfunction "OUT_S2") (pintype "output"))
    )
    (net (code "136") (name "O_BRKRQ") (class "Default")
      (node (ref "A20") (pin "K2") (pinfunction "P$2_K2") (pintype "bidirectional"))
      (node (ref "B18") (pin "P2") (pinfunction "IN_P2") (pintype "input"))
    )
    (net (code "137") (name "O_CAINCR") (class "Default")
      (node (ref "A22") (pin "M2") (pinfunction "P$2_M2") (pintype "bidirectional"))
      (node (ref "B19") (pin "K2") (pinfunction "IN_K2") (pintype "input"))
    )
    (net (code "138") (name "O_DATA00") (class "Default")
      (node (ref "A21") (pin "D2") (pinfunction "P$2_D2") (pintype "bidirectional"))
      (node (ref "B22") (pin "E2") (pinfunction "IN_E2") (pintype "input"))
    )
    (net (code "139") (name "O_DATA01") (class "Default")
      (node (ref "A21") (pin "E2") (pinfunction "P$2_E2") (pintype "bidirectional"))
      (node (ref "B22") (pin "H2") (pinfunction "IN_H2") (pintype "input"))
    )
    (net (code "140") (name "O_DATA02") (class "Default")
      (node (ref "A21") (pin "H2") (pinfunction "P$2_H2") (pintype "bidirectional"))
      (node (ref "B22") (pin "K2") (pinfunction "IN_K2") (pintype "input"))
    )
    (net (code "141") (name "O_DATA03") (class "Default")
      (node (ref "A21") (pin "K2") (pinfunction "P$2_K2") (pintype "bidirectional"))
      (node (ref "B22") (pin "M2") (pinfunction "IN_M2") (pintype "input"))
    )
    (net (code "142") (name "O_DATA04") (class "Default")
      (node (ref "A21") (pin "M2") (pinfunction "P$2_M2") (pintype "bidirectional"))
      (node (ref "B22") (pin "P2") (pinfunction "IN_P2") (pintype "input"))
    )
    (net (code "143") (name "O_DATA05") (class "Default")
      (node (ref "A21") (pin "P2") (pinfunction "P$2_P2") (pintype "bidirectional"))
      (node (ref "B22") (pin "S2") (pinfunction "IN_S2") (pintype "input"))
    )
    (net (code "144") (name "O_DATA06") (class "Default")
      (node (ref "A21") (pin "S2") (pinfunction "P$2_S2") (pintype "bidirectional"))
      (node (ref "B23") (pin "E2") (pinfunction "IN_E2") (pintype "input"))
    )
    (net (code "145") (name "O_DATA07") (class "Default")
      (node (ref "A21") (pin "T2") (pinfunction "P$2_T2") (pintype "bidirectional"))
      (node (ref "B23") (pin "H2") (pinfunction "IN_H2") (pintype "input"))
    )
    (net (code "146") (name "O_DATA08") (class "Default")
      (node (ref "A21") (pin "V2") (pinfunction "P$2_V2") (pintype "bidirectional"))
      (node (ref "B23") (pin "K2") (pinfunction "IN_K2") (pintype "input"))
    )
    (net (code "147") (name "O_DATA09") (class "Default")
      (node (ref "A22") (pin "D2") (pinfunction "P$2_D2") (pintype "bidirectional"))
      (node (ref "B23") (pin "M2") (pinfunction "IN_M2") (pintype "input"))
    )
    (net (code "148") (name "O_DATA10") (class "Default")
      (node (ref "A22") (pin "E2") (pinfunction "P$2_E2") (pintype "bidirectional"))
      (node (ref "B23") (pin "P2") (pinfunction "IN_P2") (pintype "input"))
    )
    (net (code "149") (name "O_DATA11") (class "Default")
      (node (ref "A22") (pin "H2") (pinfunction "P$2_H2") (pintype "bidirectional"))
      (node (ref "B23") (pin "S2") (pinfunction "IN_S2") (pintype "input"))
    )
    (net (code "150") (name "O_DATAIN") (class "Default")
      (node (ref "A20") (pin "M2") (pinfunction "P$2_M2") (pintype "bidirectional"))
      (node (ref "B18") (pin "S2") (pinfunction "IN_S2") (pintype "input"))
    )
    (net (code "151") (name "O_EXTA0") (class "Default")
      (node (ref "A23") (pin "H2") (pinfunction "P$2_H2") (pintype "bidirectional"))
      (node (ref "B19") (pin "S2") (pinfunction "IN_S2") (pintype "input"))
    )
    (net (code "152") (name "O_EXTA1") (class "Default")
      (node (ref "A23") (pin "E2") (pinfunction "P$2_E2") (pintype "bidirectional"))
      (node (ref "B19") (pin "P2") (pinfunction "IN_P2") (pintype "input"))
    )
    (net (code "153") (name "O_EXTA2") (class "Default")
      (node (ref "A23") (pin "D2") (pinfunction "P$2_D2") (pintype "bidirectional"))
      (node (ref "B19") (pin "M2") (pinfunction "IN_M2") (pintype "input"))
    )
    (net (code "154") (name "O_INIT") (class "Default")
      (node (ref "A14") (pin "V2") (pinfunction "P$2_V2") (pintype "bidirectional"))
      (node (ref "B09") (pin "S2") (pinfunction "OUT_S2") (pintype "output"))
    )
    (net (code "155") (name "O_IOP1") (class "Default")
      (node (ref "A14") (pin "K2") (pinfunction "P$2_K2") (pintype "bidirectional"))
      (node (ref "B08") (pin "D2") (pinfunction "OUT_D2") (pintype "output"))
    )
    (net (code "156") (name "O_IOP2") (class "Default")
      (node (ref "A14") (pin "M2") (pinfunction "P$2_M2") (pintype "bidirectional"))
      (node (ref "B08") (pin "K2") (pinfunction "OUT_K2") (pintype "output"))
    )
    (net (code "157") (name "O_IOP4") (class "Default")
      (node (ref "A14") (pin "P2") (pinfunction "P$2_P2") (pintype "bidirectional"))
      (node (ref "B08") (pin "S2") (pinfunction "OUT_S2") (pintype "output"))
    )
    (net (code "158") (name "O_IRQ") (class "Default")
      (node (ref "A18") (pin "M2") (pinfunction "P$2_M2") (pintype "bidirectional"))
      (node (ref "B18") (pin "H2") (pinfunction "IN_H2") (pintype "input"))
    )
    (net (code "159") (name "O_LINE") (class "Default")
      (node (ref "A18") (pin "V2") (pinfunction "P$2_V2") (pintype "bidirectional"))
      (node (ref "B18") (pin "M2") (pinfunction "IN_M2") (pintype "input"))
    )
    (net (code "160") (name "O_MB00") (class "Default")
      (node (ref "A07") (pin "D2") (pinfunction "OUT_D2") (pintype "output"))
      (node (ref "A15") (pin "D2") (pinfunction "P$2_D2") (pintype "bidirectional"))
    )
    (net (code "161") (name "O_MB01") (class "Default")
      (node (ref "A07") (pin "K2") (pinfunction "OUT_K2") (pintype "output"))
      (node (ref "A15") (pin "E2") (pinfunction "P$2_E2") (pintype "bidirectional"))
    )
    (net (code "162") (name "O_MB02") (class "Default")
      (node (ref "A07") (pin "S2") (pinfunction "OUT_S2") (pintype "output"))
      (node (ref "A15") (pin "H2") (pinfunction "P$2_H2") (pintype "bidirectional"))
    )
    (net (code "163") (name "O_MB03") (class "Default")
      (node (ref "A08") (pin "K2") (pinfunction "OUT_K2") (pintype "output"))
      (node (ref "A15") (pin "M2") (pinfunction "P$2_M2") (pintype "bidirectional"))
    )
    (net (code "164") (name "O_MB04") (class "Default")
      (node (ref "A09") (pin "D2") (pinfunction "OUT_D2") (pintype "output"))
      (node (ref "A15") (pin "S2") (pinfunction "P$2_S2") (pintype "bidirectional"))
    )
    (net (code "165") (name "O_MB05") (class "Default")
      (node (ref "A09") (pin "S2") (pinfunction "OUT_S2") (pintype "output"))
      (node (ref "A15") (pin "V2") (pinfunction "P$2_V2") (pintype "bidirectional"))
    )
    (net (code "166") (name "O_MB06") (class "Default")
      (node (ref "A10") (pin "K2") (pinfunction "OUT_K2") (pintype "output"))
      (node (ref "A16") (pin "E2") (pinfunction "P$2_E2") (pintype "bidirectional"))
    )
    (net (code "167") (name "O_MB07") (class "Default")
      (node (ref "A11") (pin "D2") (pinfunction "OUT_D2") (pintype "output"))
      (node (ref "A16") (pin "K2") (pinfunction "P$2_K2") (pintype "bidirectional"))
    )
    (net (code "168") (name "O_MB08") (class "Default")
      (node (ref "A11") (pin "S2") (pinfunction "OUT_S2") (pintype "output"))
      (node (ref "A16") (pin "P2") (pinfunction "P$2_P2") (pintype "bidirectional"))
    )
    (net (code "169") (name "O_MB09") (class "Default")
      (node (ref "A12") (pin "D2") (pinfunction "OUT_D2") (pintype "output"))
      (node (ref "A16") (pin "S2") (pinfunction "P$2_S2") (pintype "bidirectional"))
    )
    (net (code "170") (name "O_MB10") (class "Default")
      (node (ref "A12") (pin "K2") (pinfunction "OUT_K2") (pintype "output"))
      (node (ref "A16") (pin "T2") (pinfunction "P$2_T2") (pintype "bidirectional"))
    )
    (net (code "171") (name "O_MB11") (class "Default")
      (node (ref "A12") (pin "S2") (pinfunction "OUT_S2") (pintype "output"))
      (node (ref "A16") (pin "V2") (pinfunction "P$2_V2") (pintype "bidirectional"))
    )
    (net (code "172") (name "O_MBINCR") (class "Default")
      (node (ref "A20") (pin "T2") (pinfunction "P$2_T2") (pintype "bidirectional"))
      (node (ref "B19") (pin "E2") (pinfunction "IN_E2") (pintype "input"))
    )
    (net (code "173") (name "O_RUN") (class "Default")
      (node (ref "A18") (pin "S2") (pinfunction "P$2_S2") (pintype "bidirectional"))
      (node (ref "B14") (pin "D2") (pinfunction "OUT_D2") (pintype "output"))
    )
    (net (code "174") (name "O_SKIP") (class "Default")
      (node (ref "A18") (pin "K2") (pinfunction "P$2_K2") (pintype "bidirectional"))
      (node (ref "B18") (pin "E2") (pinfunction "IN_E2") (pintype "input"))
    )
    (net (code "175") (name "O_TS1") (class "Default")
      (node (ref "A14") (pin "T2") (pinfunction "P$2_T2") (pintype "bidirectional"))
      (node (ref "B09") (pin "K2") (pinfunction "OUT_K2") (pintype "output"))
    )
    (net (code "176") (name "O_TS3") (class "Default")
      (node (ref "A14") (pin "S2") (pinfunction "P$2_S2") (pintype "bidirectional"))
      (node (ref "B09") (pin "D2") (pinfunction "OUT_D2") (pintype "output"))
    )
    (net (code "177") (name "O_TT_INST") (class "Default")
      (node (ref "A18") (pin "T2") (pinfunction "P$2_T2") (pintype "bidirectional"))
      (node (ref "B14") (pin "K2") (pinfunction "OUT_K2") (pintype "output"))
    )
    (net (code "178") (name "O_WCOV") (class "Default")
      (node (ref "A22") (pin "P2") (pinfunction "P$2_P2") (pintype "bidirectional"))
      (node (ref "B15") (pin "K2") (pinfunction "OUT_K2") (pintype "output"))
    )
    (net (code "180") (name "unconnected-(A07A-SLOW-PadE2)") (class "Default")
      (node (ref "A07") (pin "E2") (pinfunction "SLOW_E2") (pintype "passive"))
    )
    (net (code "181") (name "unconnected-(A07D-SLOW-PadL2)") (class "Default")
      (node (ref "A07") (pin "L2") (pinfunction "SLOW_L2") (pintype "passive"))
    )
    (net (code "182") (name "unconnected-(A07E-SLOW-PadR2)") (class "Default")
      (node (ref "A07") (pin "R2") (pinfunction "SLOW_R2") (pintype "passive"))
    )
    (net (code "183") (name "unconnected-(A08A-SLOW-PadE2)") (class "Default")
      (node (ref "A08") (pin "E2") (pinfunction "SLOW_E2") (pintype "passive"))
    )
    (net (code "184") (name "unconnected-(A08D-SLOW-PadL2)") (class "Default")
      (node (ref "A08") (pin "L2") (pinfunction "SLOW_L2") (pintype "passive"))
    )
    (net (code "185") (name "unconnected-(A08E-SLOW-PadR2)") (class "Default")
      (node (ref "A08") (pin "R2") (pinfunction "SLOW_R2") (pintype "passive"))
    )
    (net (code "186") (name "unconnected-(A09A-SLOW-PadE2)") (class "Default")
      (node (ref "A09") (pin "E2") (pinfunction "SLOW_E2") (pintype "passive"))
    )
    (net (code "187") (name "unconnected-(A09D-SLOW-PadL2)") (class "Default")
      (node (ref "A09") (pin "L2") (pinfunction "SLOW_L2") (pintype "passive"))
    )
    (net (code "188") (name "unconnected-(A09E-SLOW-PadR2)") (class "Default")
      (node (ref "A09") (pin "R2") (pinfunction "SLOW_R2") (pintype "passive"))
    )
    (net (code "189") (name "unconnected-(A10A-SLOW-PadE2)") (class "Default")
      (node (ref "A10") (pin "E2") (pinfunction "SLOW_E2") (pintype "passive"))
    )
    (net (code "190") (name "unconnected-(A10D-SLOW-PadL2)") (class "Default")
      (node (ref "A10") (pin "L2") (pinfunction "SLOW_L2") (pintype "passive"))
    )
    (net (code "191") (name "unconnected-(A10E-SLOW-PadR2)") (class "Default")
      (node (ref "A10") (pin "R2") (pinfunction "SLOW_R2") (pintype "passive"))
    )
    (net (code "192") (name "unconnected-(A11A-SLOW-PadE2)") (class "Default")
      (node (ref "A11") (pin "E2") (pinfunction "SLOW_E2") (pintype "passive"))
    )
    (net (code "193") (name "unconnected-(A11D-SLOW-PadL2)") (class "Default")
      (node (ref "A11") (pin "L2") (pinfunction "SLOW_L2") (pintype "passive"))
    )
    (net (code "194") (name "unconnected-(A11E-SLOW-PadR2)") (class "Default")
      (node (ref "A11") (pin "R2") (pinfunction "SLOW_R2") (pintype "passive"))
    )
    (net (code "195") (name "unconnected-(A12A-SLOW-PadE2)") (class "Default")
      (node (ref "A12") (pin "E2") (pinfunction "SLOW_E2") (pintype "passive"))
    )
    (net (code "196") (name "unconnected-(A12D-SLOW-PadL2)") (class "Default")
      (node (ref "A12") (pin "L2") (pinfunction "SLOW_L2") (pintype "passive"))
    )
    (net (code "197") (name "unconnected-(A12E-SLOW-PadR2)") (class "Default")
      (node (ref "A12") (pin "R2") (pinfunction "SLOW_R2") (pintype "passive"))
    )
    (net (code "198") (name "unconnected-(B08A-SLOW-PadE2)") (class "Default")
      (node (ref "B08") (pin "E2") (pinfunction "SLOW_E2") (pintype "passive"))
    )
    (net (code "199") (name "unconnected-(B08D-SLOW-PadL2)") (class "Default")
      (node (ref "B08") (pin "L2") (pinfunction "SLOW_L2") (pintype "passive"))
    )
    (net (code "200") (name "unconnected-(B08E-SLOW-PadR2)") (class "Default")
      (node (ref "B08") (pin "R2") (pinfunction "SLOW_R2") (pintype "passive"))
    )
    (net (code "201") (name "unconnected-(B09A-SLOW-PadE2)") (class "Default")
      (node (ref "B09") (pin "E2") (pinfunction "SLOW_E2") (pintype "passive"))
    )
    (net (code "202") (name "unconnected-(B09D-SLOW-PadL2)") (class "Default")
      (node (ref "B09") (pin "L2") (pinfunction "SLOW_L2") (pintype "passive"))
    )
    (net (code "203") (name "unconnected-(B09E-SLOW-PadR2)") (class "Default")
      (node (ref "B09") (pin "R2") (pinfunction "SLOW_R2") (pintype "passive"))
    )
    (net (code "204") (name "unconnected-(B10A-SLOW-PadE2)") (class "Default")
      (node (ref "B10") (pin "E2") (pinfunction "SLOW_E2") (pintype "passive"))
    )
    (net (code "205") (name "unconnected-(B10D-SLOW-PadL2)") (class "Default")
      (node (ref "B10") (pin "L2") (pinfunction "SLOW_L2") (pintype "passive"))
    )
    (net (code "206") (name "unconnected-(B10E-SLOW-PadR2)") (class "Default")
      (node (ref "B10") (pin "R2") (pinfunction "SLOW_R2") (pintype "passive"))
    )
    (net (code "207") (name "unconnected-(B11A-SLOW-PadE2)") (class "Default")
      (node (ref "B11") (pin "E2") (pinfunction "SLOW_E2") (pintype "passive"))
    )
    (net (code "208") (name "unconnected-(B11D-SLOW-PadL2)") (class "Default")
      (node (ref "B11") (pin "L2") (pinfunction "SLOW_L2") (pintype "passive"))
    )
    (net (code "209") (name "unconnected-(B11E-SLOW-PadR2)") (class "Default")
      (node (ref "B11") (pin "R2") (pinfunction "SLOW_R2") (pintype "passive"))
    )
    (net (code "210") (name "unconnected-(B12A-SLOW-PadE2)") (class "Default")
      (node (ref "B12") (pin "E2") (pinfunction "SLOW_E2") (pintype "passive"))
    )
    (net (code "211") (name "unconnected-(B12D-SLOW-PadL2)") (class "Default")
      (node (ref "B12") (pin "L2") (pinfunction "SLOW_L2") (pintype "passive"))
    )
    (net (code "212") (name "unconnected-(B12E-SLOW-PadR2)") (class "Default")
      (node (ref "B12") (pin "R2") (pinfunction "SLOW_R2") (pintype "passive"))
    )
    (net (code "213") (name "unconnected-(B13A-SLOW-PadE2)") (class "Default")
      (node (ref "B13") (pin "E2") (pinfunction "SLOW_E2") (pintype "passive"))
    )
    (net (code "214") (name "unconnected-(B13D-SLOW-PadL2)") (class "Default")
      (node (ref "B13") (pin "L2") (pinfunction "SLOW_L2") (pintype "passive"))
    )
    (net (code "215") (name "unconnected-(B13E-SLOW-PadR2)") (class "Default")
      (node (ref "B13") (pin "R2") (pinfunction "SLOW_R2") (pintype "passive"))
    )
    (net (code "216") (name "unconnected-(B14A-SLOW-PadE2)") (class "Default")
      (node (ref "B14") (pin "E2") (pinfunction "SLOW_E2") (pintype "passive"))
    )
    (net (code "217") (name "unconnected-(B14D-SLOW-PadL2)") (class "Default")
      (node (ref "B14") (pin "L2") (pinfunction "SLOW_L2") (pintype "passive"))
    )
    (net (code "218") (name "unconnected-(B14E-SLOW-PadR2)") (class "Default")
      (node (ref "B14") (pin "R2") (pinfunction "SLOW_R2") (pintype "passive"))
    )
    (net (code "219") (name "unconnected-(B15A-SLOW-PadE2)") (class "Default")
      (node (ref "B15") (pin "E2") (pinfunction "SLOW_E2") (pintype "passive"))
    )
    (net (code "220") (name "unconnected-(B15D-SLOW-PadL2)") (class "Default")
      (node (ref "B15") (pin "L2") (pinfunction "SLOW_L2") (pintype "passive"))
    )
    (net (code "221") (name "~{I_MB03}") (class "Default")
      (node (ref "A02") (pin "H1") (pinfunction "P$2_H1") (pintype "bidirectional"))
      (node (ref "A06") (pin "H1") (pinfunction "CATHODE_H1") (pintype "passive"))
      (node (ref "A08") (pin "H2") (pinfunction "IN2_H2") (pintype "input"))
      (node (ref "B02") (pin "H1") (pinfunction "P$2_H1") (pintype "bidirectional"))
    )
    (net (code "222") (name "~{I_MB04}") (class "Default")
      (node (ref "A02") (pin "L1") (pinfunction "P$2_L1") (pintype "bidirectional"))
      (node (ref "A06") (pin "L1") (pinfunction "CATHODE_L1") (pintype "passive"))
      (node (ref "A08") (pin "U2") (pinfunction "IN2_U2") (pintype "input"))
      (node (ref "B02") (pin "L1") (pinfunction "P$2_L1") (pintype "bidirectional"))
    )
    (net (code "223") (name "~{I_MB05}") (class "Default")
      (node (ref "A02") (pin "P1") (pinfunction "P$2_P1") (pintype "bidirectional"))
      (node (ref "A06") (pin "P1") (pinfunction "CATHODE_P1") (pintype "passive"))
      (node (ref "A09") (pin "N2") (pinfunction "IN2_N2") (pintype "input"))
      (node (ref "B02") (pin "P1") (pinfunction "P$2_P1") (pintype "bidirectional"))
    )
    (net (code "224") (name "~{I_MB06}") (class "Default")
      (node (ref "A02") (pin "D2") (pinfunction "P$2_D2") (pintype "bidirectional"))
      (node (ref "A06") (pin "D2") (pinfunction "CATHODE_D2") (pintype "passive"))
      (node (ref "A10") (pin "H2") (pinfunction "IN2_H2") (pintype "input"))
      (node (ref "B02") (pin "D2") (pinfunction "P$2_D2") (pintype "bidirectional"))
    )
    (net (code "225") (name "~{I_MB07}") (class "Default")
      (node (ref "A02") (pin "H2") (pinfunction "P$2_H2") (pintype "bidirectional"))
      (node (ref "A06") (pin "H2") (pinfunction "CATHODE_H2") (pintype "passive"))
      (node (ref "A10") (pin "U2") (pinfunction "IN2_U2") (pintype "input"))
      (node (ref "B02") (pin "H2") (pinfunction "P$2_H2") (pintype "bidirectional"))
    )
    (net (code "226") (name "~{I_MB08}") (class "Default")
      (node (ref "A02") (pin "M2") (pinfunction "P$2_M2") (pintype "bidirectional"))
      (node (ref "A06") (pin "M2") (pinfunction "CATHODE_M2") (pintype "passive"))
      (node (ref "A11") (pin "N2") (pinfunction "IN2_N2") (pintype "input"))
      (node (ref "B02") (pin "M2") (pinfunction "P$2_M2") (pintype "bidirectional"))
    )
    (net (code "227") (name "~{O_MB03}") (class "Default")
      (node (ref "A08") (pin "D2") (pinfunction "OUT_D2") (pintype "output"))
      (node (ref "A15") (pin "K2") (pinfunction "P$2_K2") (pintype "bidirectional"))
    )
    (net (code "228") (name "~{O_MB04}") (class "Default")
      (node (ref "A08") (pin "S2") (pinfunction "OUT_S2") (pintype "output"))
      (node (ref "A15") (pin "P2") (pinfunction "P$2_P2") (pintype "bidirectional"))
    )
    (net (code "229") (name "~{O_MB05}") (class "Default")
      (node (ref "A09") (pin "K2") (pinfunction "OUT_K2") (pintype "output"))
      (node (ref "A15") (pin "T2") (pinfunction "P$2_T2") (pintype "bidirectional"))
    )
    (net (code "230") (name "~{O_MB06}") (class "Default")
      (node (ref "A10") (pin "D2") (pinfunction "OUT_D2") (pintype "output"))
      (node (ref "A16") (pin "D2") (pinfunction "P$2_D2") (pintype "bidirectional"))
    )
    (net (code "231") (name "~{O_MB07}") (class "Default")
      (node (ref "A10") (pin "S2") (pinfunction "OUT_S2") (pintype "output"))
      (node (ref "A16") (pin "H2") (pinfunction "P$2_H2") (pintype "bidirectional"))
    )
    (net (code "232") (name "~{O_MB08}") (class "Default")
      (node (ref "A11") (pin "K2") (pinfunction "OUT_K2") (pintype "output"))
      (node (ref "A16") (pin "M2") (pinfunction "P$2_M2") (pintype "bidirectional"))
    )
  )
)
